# DAC_STM32_Board_v6_1_-_AD5391.net
KiCad netlist of a schematic drawn in EAGLE
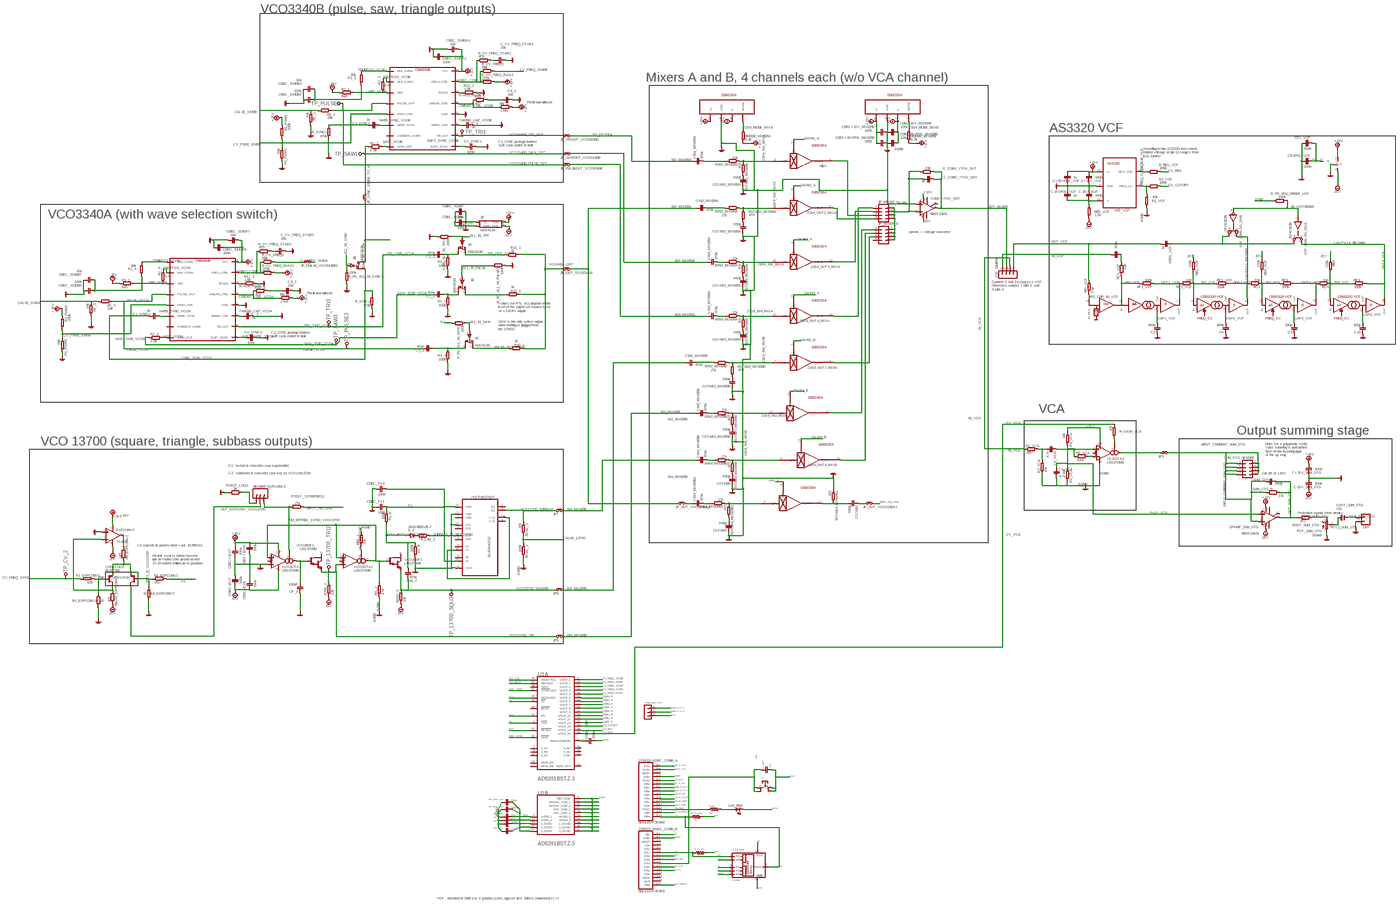
[diagram p0: schematic, sheet 1, overview]
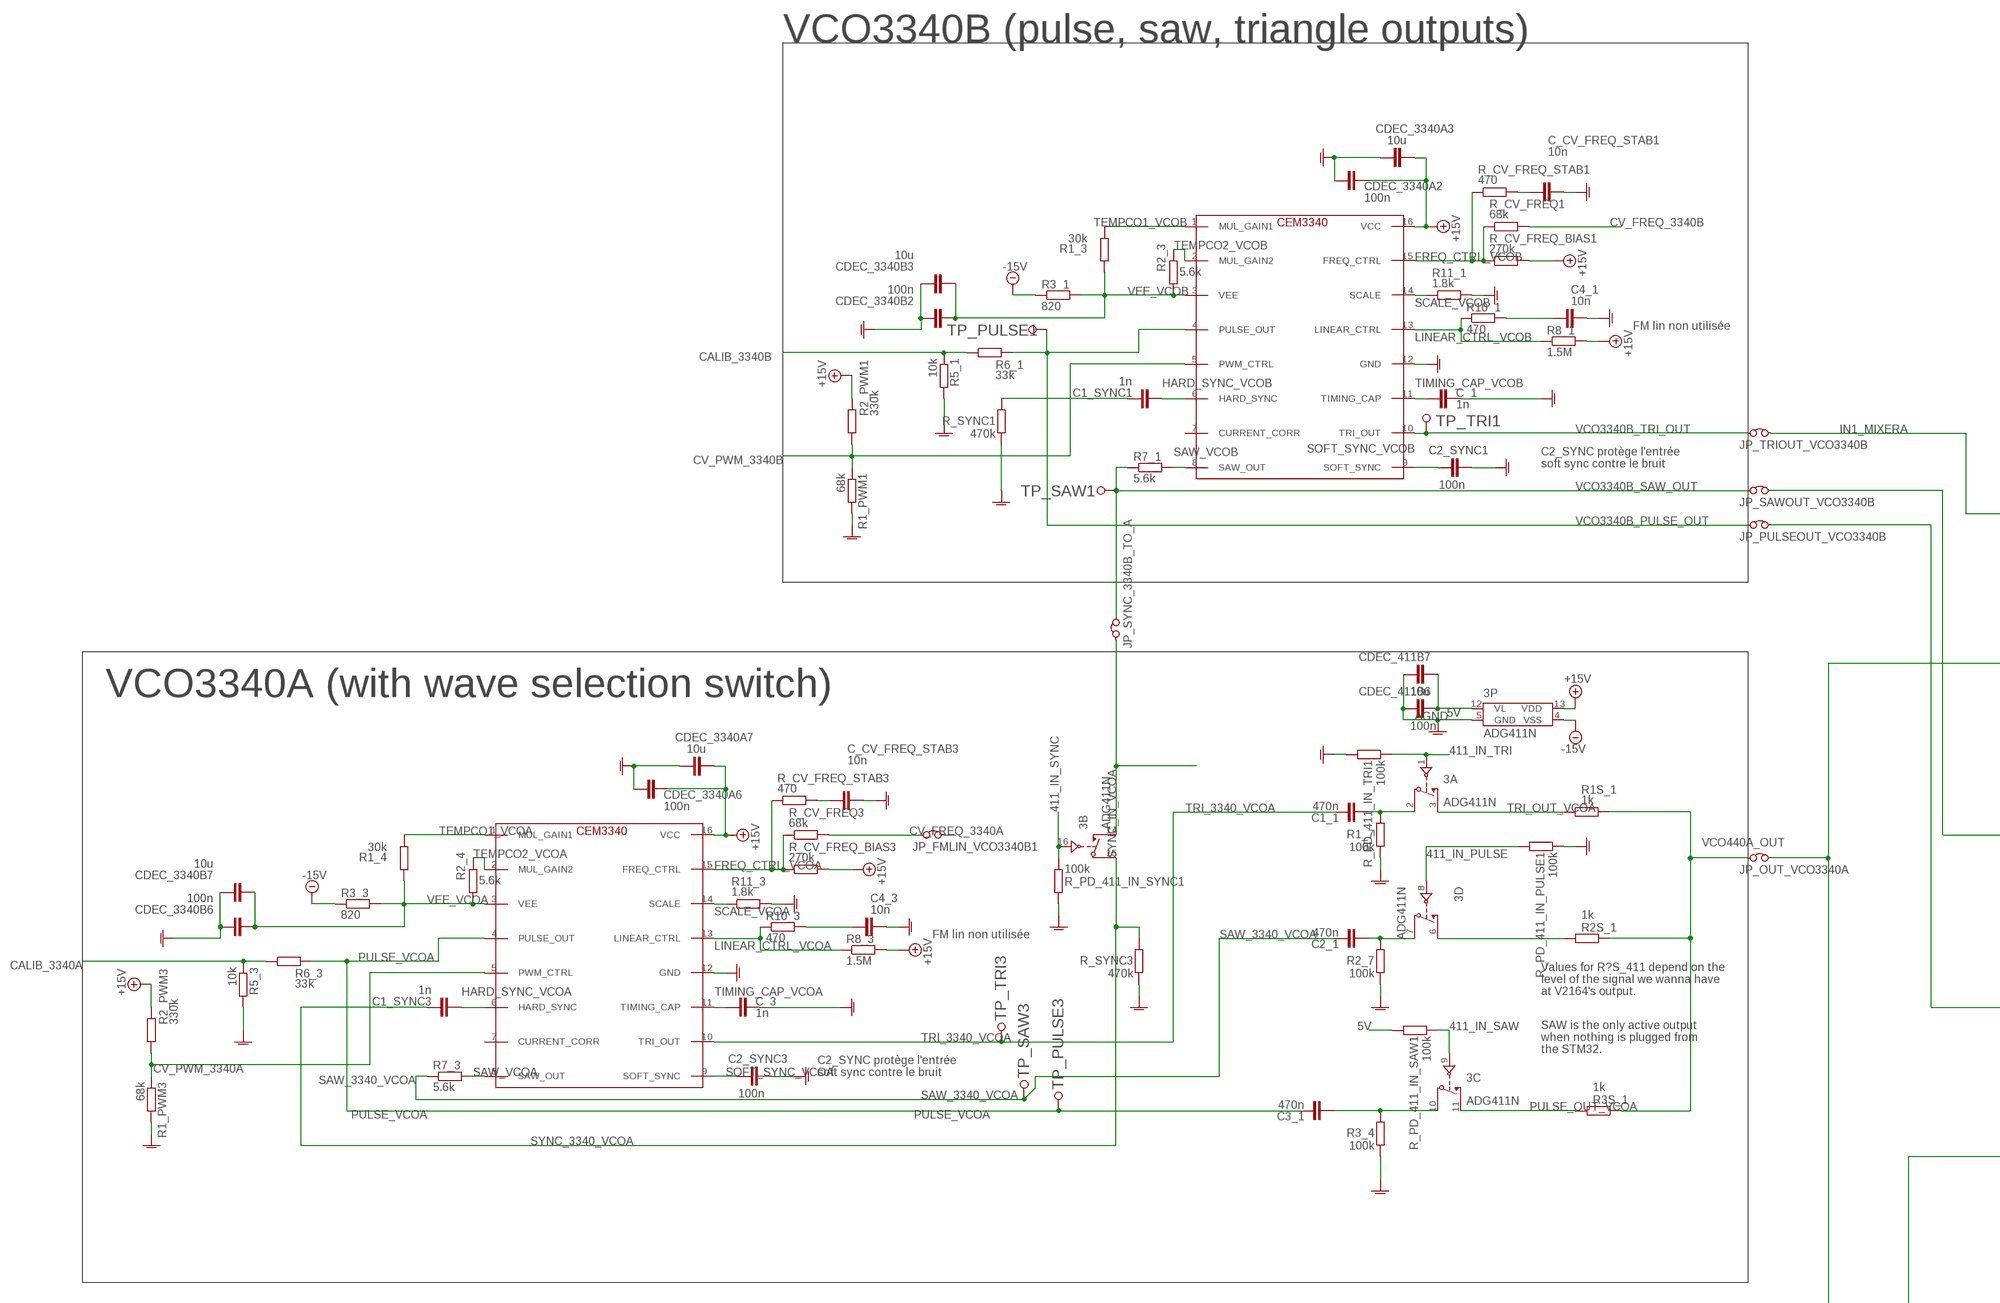
[diagram p1: schematic, sheet 1, part 1 of 4]
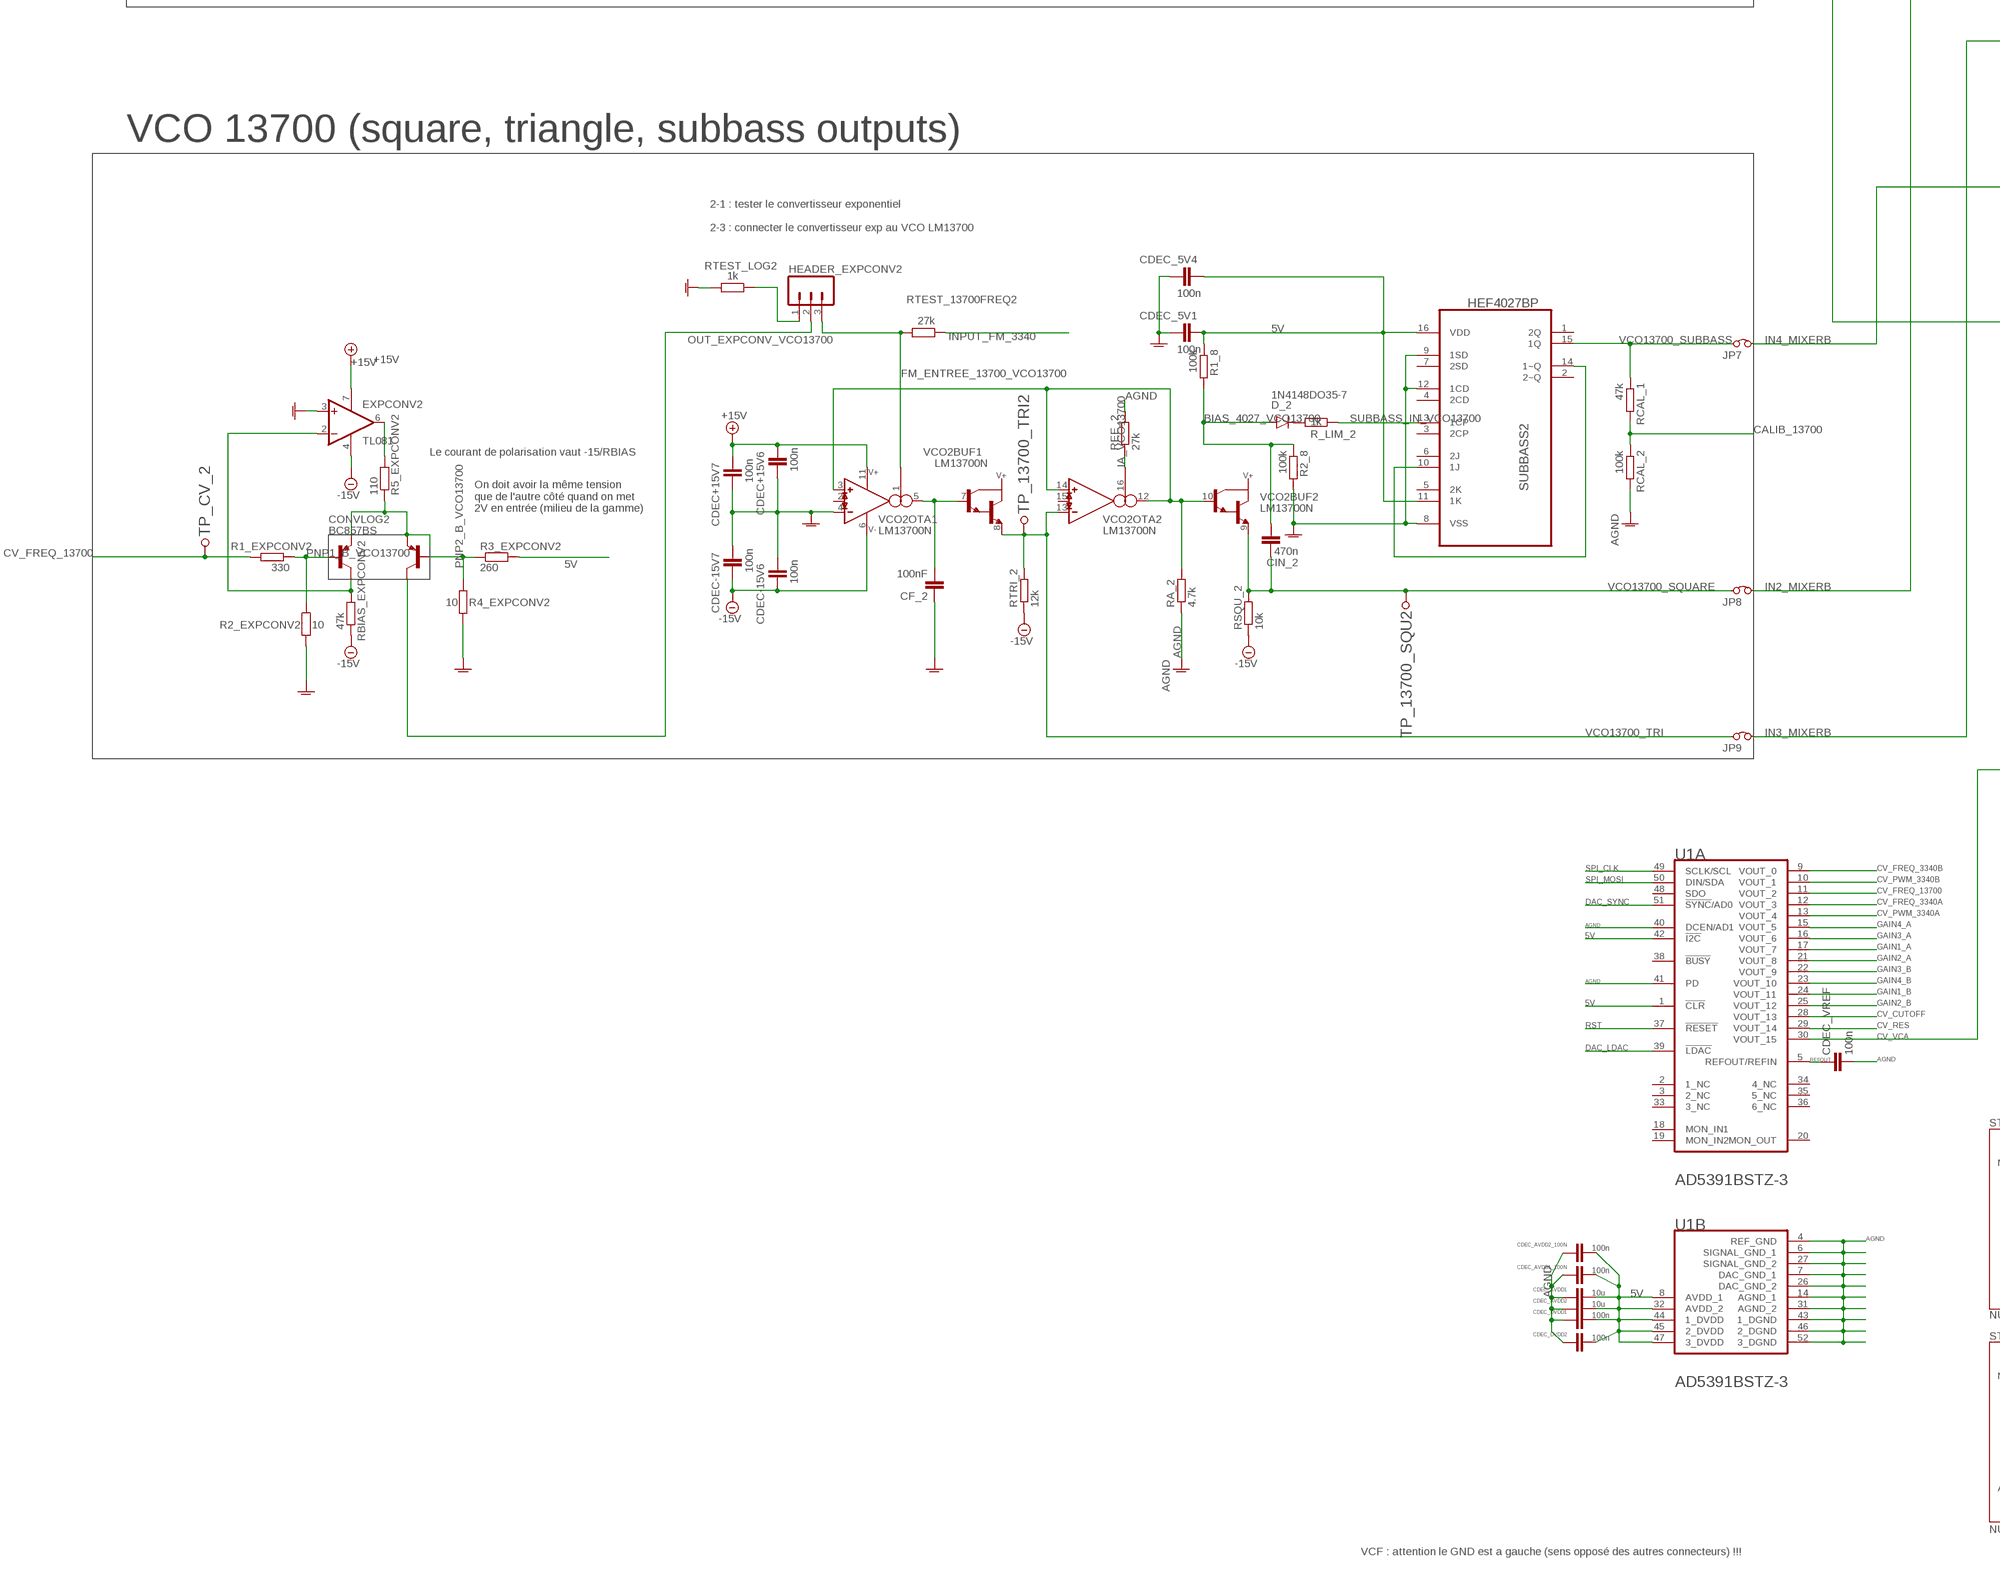
[diagram p2: schematic, sheet 1, part 2 of 4]
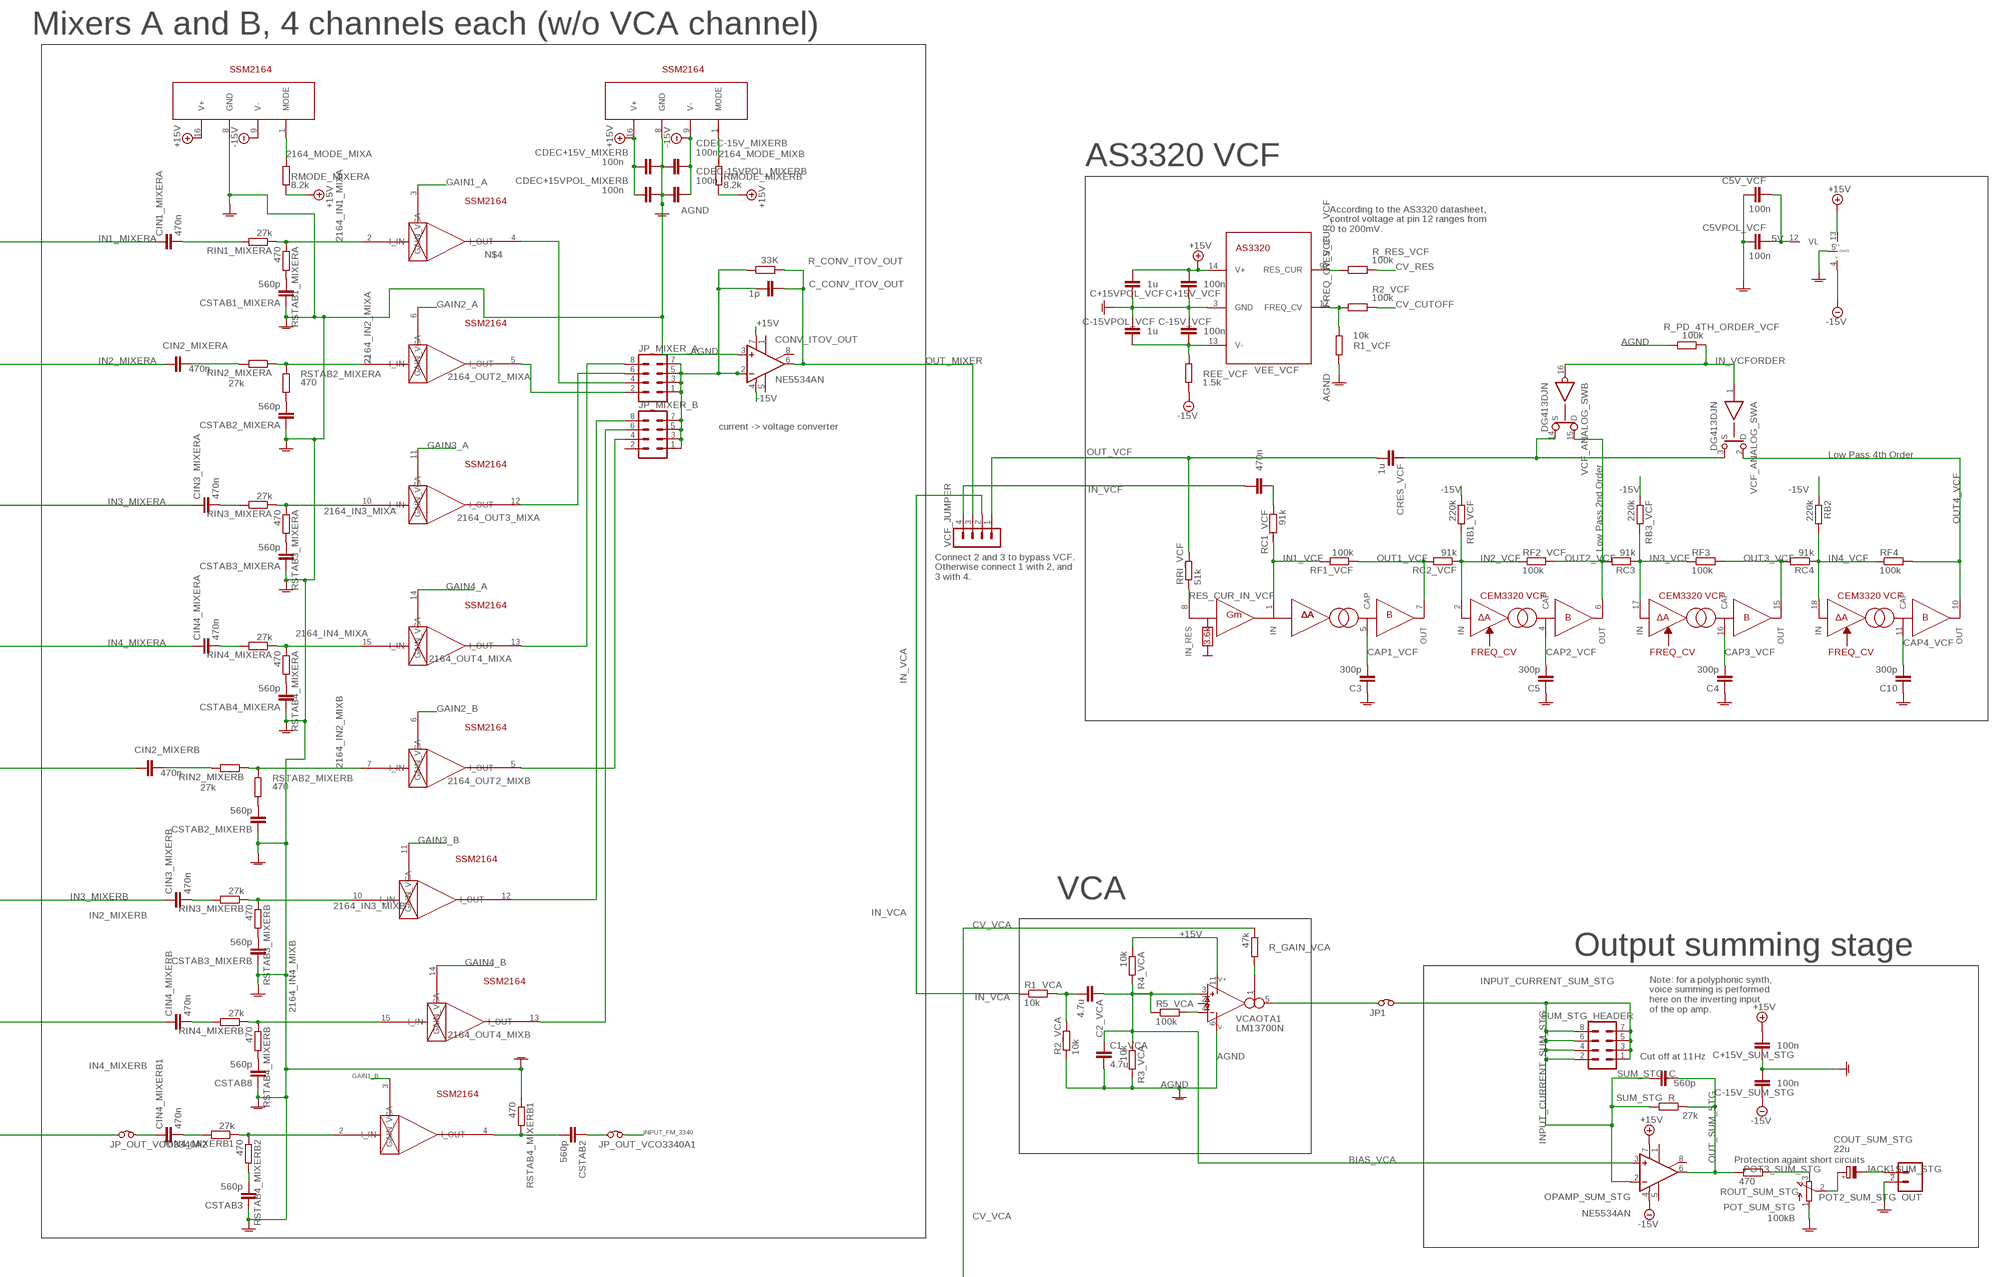
[diagram p3: schematic, sheet 1, part 3 of 4]
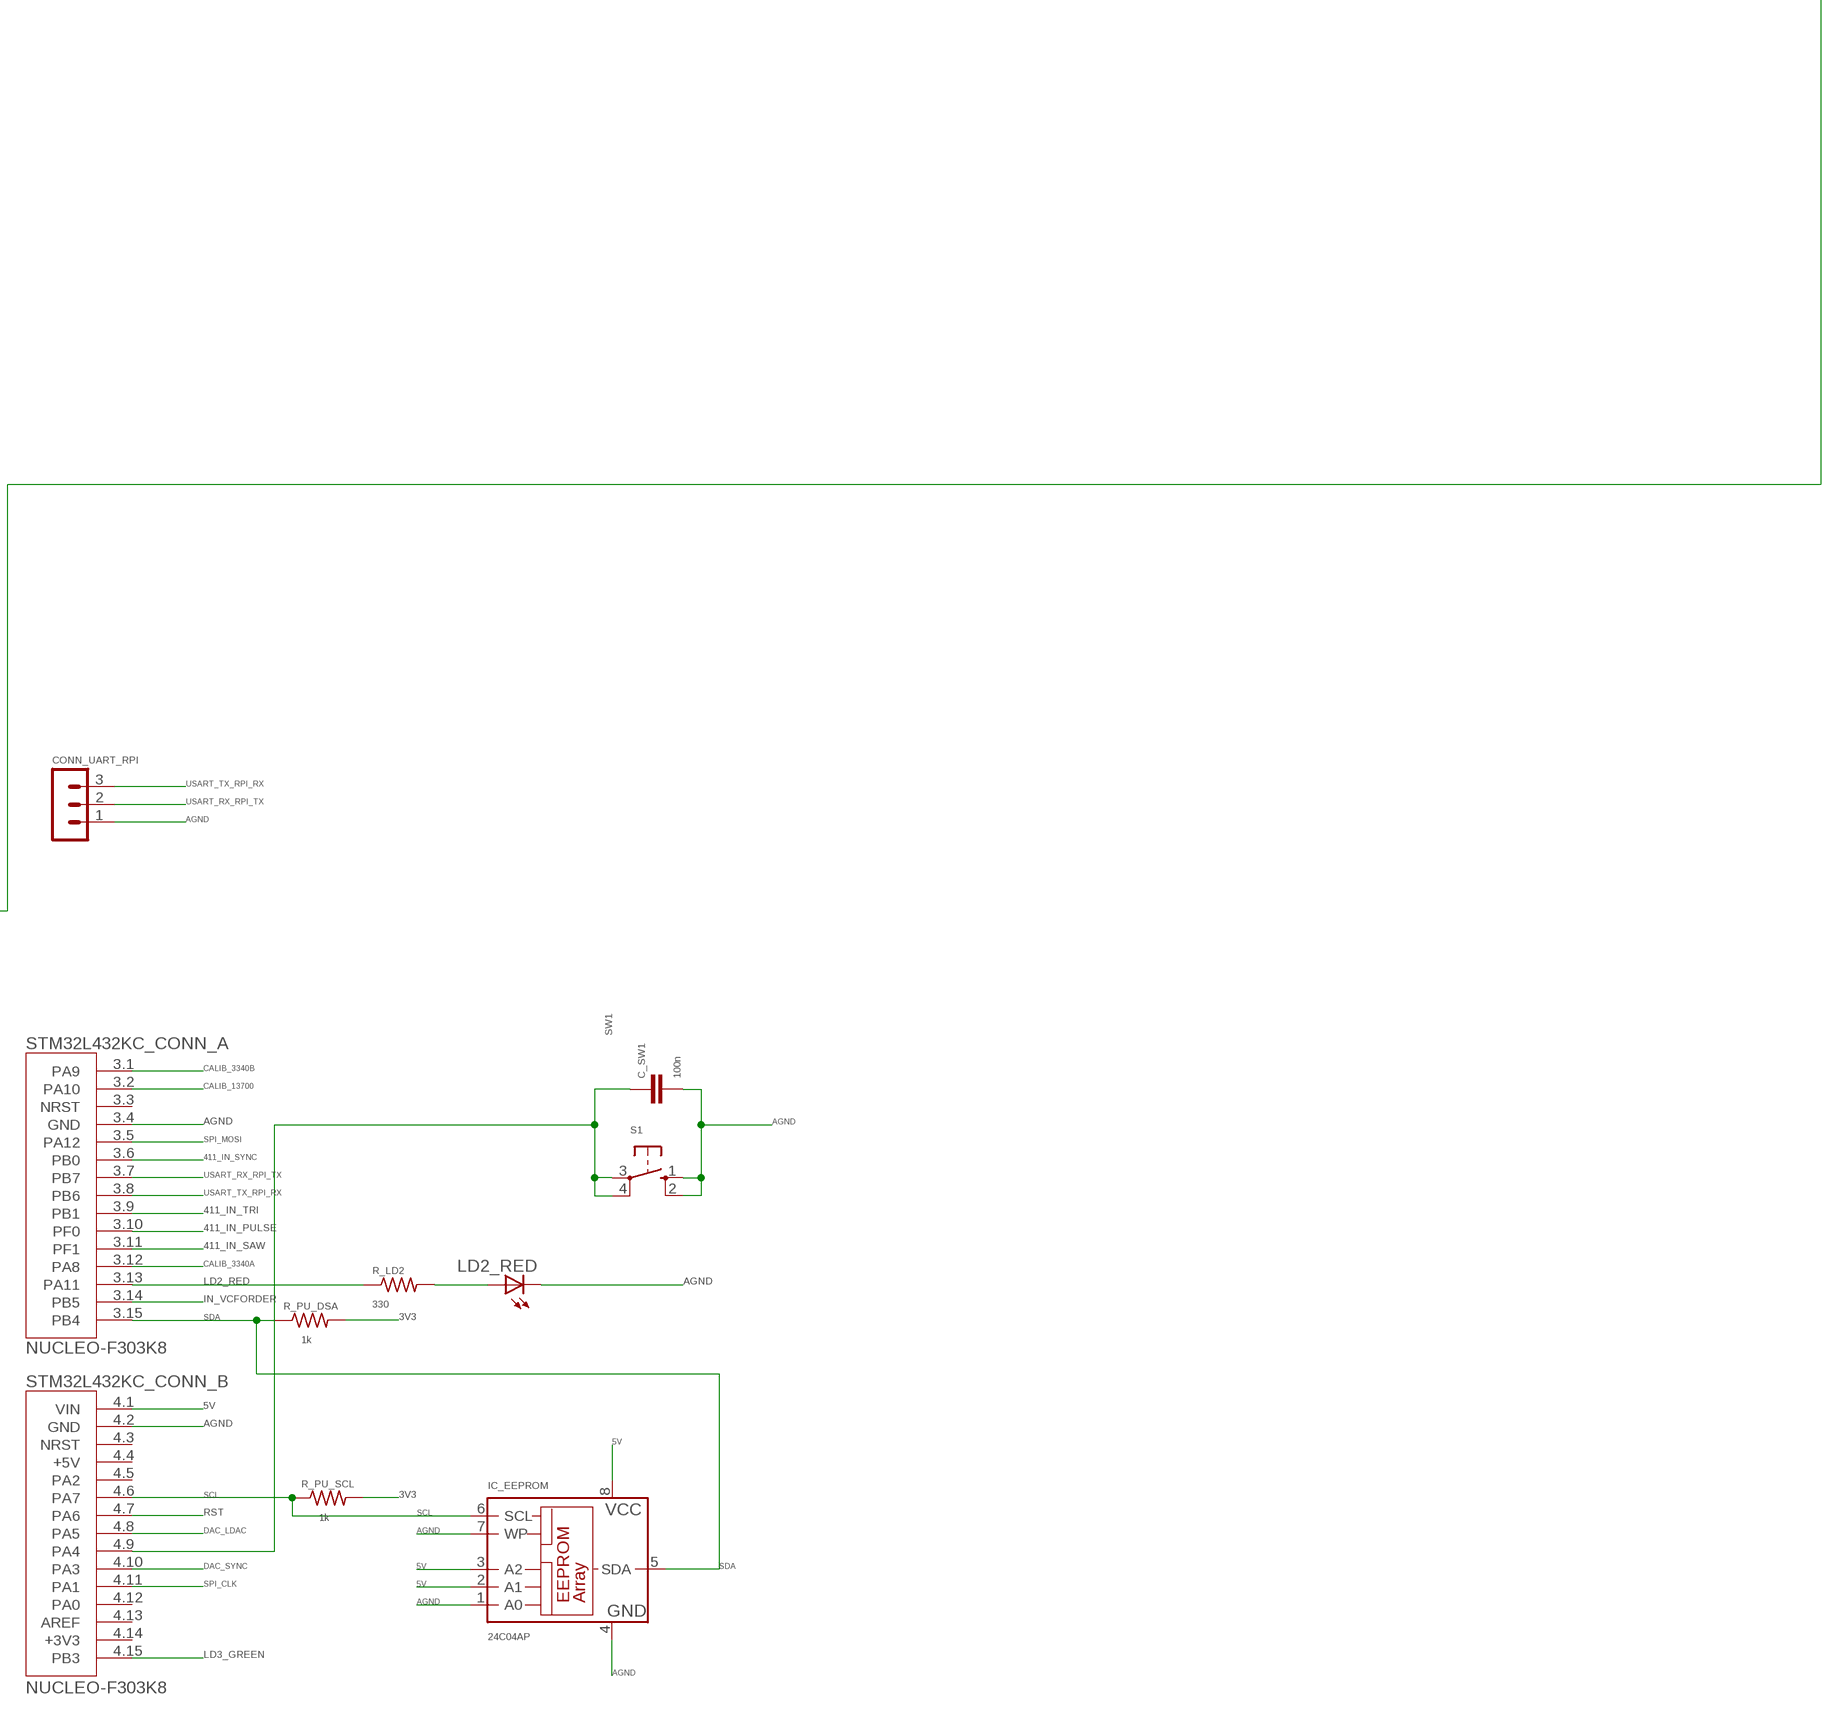
[diagram p4: schematic, sheet 1, part 4 of 4]

(export (version "E")
  (design (tool "Eeschema 10.0.6"))
  (components
    (comp (ref "3")
      (value "ADG411N")
      (footprint "eagle-import:DIL16")
      (fields (field (name "MF") "ALTERA CORPORATION") (field (name "MPN") "ADG411BN"))
      (libsource (lib "eagle-import") (part "ADG411N"))
    )
    (comp (ref "3340A")
      (value "CEM3340")
      (footprint "eagle-import:DIL16")
      (libsource (lib "eagle-import") (part "CEM3340"))
    )
    (comp (ref "3340B")
      (value "CEM3340")
      (footprint "eagle-import:DIL16")
      (libsource (lib "eagle-import") (part "CEM3340"))
    )
    (comp (ref "C+15VPOL_VCF")
      (value "1u")
      (footprint "eagle-import:C075-032X103")
      (libsource (lib "eagle-import") (part "rcl_334_C-EU075-032X103"))
    )
    (comp (ref "C+15V_SUM_STG")
      (value "100n")
      (footprint "eagle-import:C075-032X103")
      (libsource (lib "eagle-import") (part "rcl_334_C-EU075-032X103"))
    )
    (comp (ref "C+15V_VCF")
      (value "100n")
      (footprint "eagle-import:C075-032X103")
      (libsource (lib "eagle-import") (part "rcl_334_C-EU075-032X103"))
    )
    (comp (ref "C-15VPOL_VCF")
      (value "1u")
      (footprint "eagle-import:C075-032X103")
      (libsource (lib "eagle-import") (part "rcl_334_C-EU075-032X103"))
    )
    (comp (ref "C-15V_SUM_STG")
      (value "100n")
      (footprint "eagle-import:C075-032X103")
      (libsource (lib "eagle-import") (part "rcl_334_C-EU075-032X103"))
    )
    (comp (ref "C-15V_VCF")
      (value "100n")
      (footprint "eagle-import:C075-032X103")
      (libsource (lib "eagle-import") (part "rcl_334_C-EU075-032X103"))
    )
    (comp (ref "C1_1")
      (value "470n")
      (footprint "eagle-import:C075-032X103")
      (libsource (lib "eagle-import") (part "rcl_334_C-EU075-032X103"))
    )
    (comp (ref "C1_SYNC1")
      (value "1n")
      (footprint "eagle-import:C075-032X103")
      (libsource (lib "eagle-import") (part "rcl_334_C-EU075-032X103"))
    )
    (comp (ref "C1_SYNC3")
      (value "1n")
      (footprint "eagle-import:C075-032X103")
      (libsource (lib "eagle-import") (part "rcl_334_C-EU075-032X103"))
    )
    (comp (ref "C1_VCA")
      (value "4.7u")
      (footprint "eagle-import:C050-030X075")
      (libsource (lib "eagle-import") (part "rcl_334_C-EU050-030X075"))
    )
    (comp (ref "C2_1")
      (value "470n")
      (footprint "eagle-import:C075-032X103")
      (libsource (lib "eagle-import") (part "rcl_334_C-EU075-032X103"))
    )
    (comp (ref "C2_SYNC1")
      (value "100n")
      (footprint "eagle-import:C075-032X103")
      (libsource (lib "eagle-import") (part "rcl_334_C-EU075-032X103"))
    )
    (comp (ref "C2_SYNC3")
      (value "100n")
      (footprint "eagle-import:C050-025X075")
      (libsource (lib "eagle-import") (part "rcl_334_C-EU050-025X075"))
    )
    (comp (ref "C2_VCA")
      (value "4.7u")
      (footprint "eagle-import:C050-030X075")
      (libsource (lib "eagle-import") (part "rcl_334_C-EU050-030X075"))
    )
    (comp (ref "C3")
      (value "300p")
      (footprint "eagle-import:C075-032X103")
      (libsource (lib "eagle-import") (part "rcl_334_C-EU075-032X103"))
    )
    (comp (ref "C3_1")
      (value "470n")
      (footprint "eagle-import:C102-043X133")
      (libsource (lib "eagle-import") (part "rcl_334_C-EU102-043X133"))
    )
    (comp (ref "C4")
      (value "300p")
      (footprint "eagle-import:C075-032X103")
      (libsource (lib "eagle-import") (part "rcl_334_C-EU075-032X103"))
    )
    (comp (ref "C4_1")
      (value "10n")
      (footprint "eagle-import:C050-025X075")
      (libsource (lib "eagle-import") (part "rcl_334_C-EU050-025X075"))
    )
    (comp (ref "C4_3")
      (value "10n")
      (footprint "eagle-import:C050-025X075")
      (libsource (lib "eagle-import") (part "rcl_334_C-EU050-025X075"))
    )
    (comp (ref "C5")
      (value "300p")
      (footprint "eagle-import:C075-032X103")
      (libsource (lib "eagle-import") (part "rcl_334_C-EU075-032X103"))
    )
    (comp (ref "C5VPOL_VCF")
      (value "100n")
      (footprint "eagle-import:C075-032X103")
      (libsource (lib "eagle-import") (part "rcl_334_C-EU075-032X103"))
    )
    (comp (ref "C5V_VCF")
      (value "100n")
      (footprint "eagle-import:C075-032X103")
      (libsource (lib "eagle-import") (part "rcl_334_C-EU075-032X103"))
    )
    (comp (ref "C10")
      (value "300p")
      (footprint "eagle-import:C075-032X103")
      (libsource (lib "eagle-import") (part "rcl_334_C-EU075-032X103"))
    )
    (comp (ref "CDEC+15V6")
      (value "100n")
      (footprint "eagle-import:C075-032X103")
      (libsource (lib "eagle-import") (part "rcl_334_C-EU075-032X103"))
    )
    (comp (ref "CDEC+15V7")
      (value "100n")
      (footprint "eagle-import:C050-025X075")
      (libsource (lib "eagle-import") (part "rcl_334_C-EU050-025X075"))
    )
    (comp (ref "CDEC+15VPOL_MIXERB")
      (value "100n")
      (footprint "eagle-import:C075-032X103")
      (libsource (lib "eagle-import") (part "rcl_334_C-EU075-032X103"))
    )
    (comp (ref "CDEC+15V_MIXERB")
      (value "100n")
      (footprint "eagle-import:C050-030X075")
      (libsource (lib "eagle-import") (part "rcl_334_C-EU050-030X075"))
    )
    (comp (ref "CDEC-15V6")
      (value "100n")
      (footprint "eagle-import:C050-025X075")
      (libsource (lib "eagle-import") (part "rcl_334_C-EU050-025X075"))
    )
    (comp (ref "CDEC-15V7")
      (value "100n")
      (footprint "eagle-import:C075-032X103")
      (libsource (lib "eagle-import") (part "rcl_334_C-EU075-032X103"))
    )
    (comp (ref "CDEC-15VPOL_MIXERB")
      (value "100n")
      (footprint "eagle-import:C050-030X075")
      (libsource (lib "eagle-import") (part "rcl_334_C-EU050-030X075"))
    )
    (comp (ref "CDEC-15V_MIXERB")
      (value "100n")
      (footprint "eagle-import:C050-030X075")
      (libsource (lib "eagle-import") (part "rcl_334_C-EU050-030X075"))
    )
    (comp (ref "CDEC_5V1")
      (value "100n")
      (footprint "eagle-import:C050-025X075")
      (libsource (lib "eagle-import") (part "rcl_334_C-EU050-025X075"))
    )
    (comp (ref "CDEC_5V4")
      (value "100n")
      (footprint "eagle-import:C050-025X075")
      (libsource (lib "eagle-import") (part "rcl_334_C-EU050-025X075"))
    )
    (comp (ref "CDEC_411B6")
      (value "100n")
      (footprint "eagle-import:C050-025X075")
      (libsource (lib "eagle-import") (part "rcl_334_C-EU050-025X075"))
    )
    (comp (ref "CDEC_411B7")
      (value "10u")
      (footprint "eagle-import:C050-025X075")
      (libsource (lib "eagle-import") (part "rcl_334_C-EU050-025X075"))
    )
    (comp (ref "CDEC_3340A2")
      (value "100n")
      (footprint "eagle-import:C050-025X075")
      (libsource (lib "eagle-import") (part "rcl_334_C-EU050-025X075"))
    )
    (comp (ref "CDEC_3340A3")
      (value "10u")
      (footprint "eagle-import:C075-032X103")
      (libsource (lib "eagle-import") (part "rcl_334_C-EU075-032X103"))
    )
    (comp (ref "CDEC_3340A6")
      (value "100n")
      (footprint "eagle-import:C050-025X075")
      (libsource (lib "eagle-import") (part "rcl_334_C-EU050-025X075"))
    )
    (comp (ref "CDEC_3340A7")
      (value "10u")
      (footprint "eagle-import:C050-025X075")
      (libsource (lib "eagle-import") (part "rcl_334_C-EU050-025X075"))
    )
    (comp (ref "CDEC_3340B2")
      (value "100n")
      (footprint "eagle-import:C050-025X075")
      (libsource (lib "eagle-import") (part "rcl_334_C-EU050-025X075"))
    )
    (comp (ref "CDEC_3340B3")
      (value "10u")
      (footprint "eagle-import:C050-025X075")
      (libsource (lib "eagle-import") (part "rcl_334_C-EU050-025X075"))
    )
    (comp (ref "CDEC_3340B6")
      (value "100n")
      (footprint "eagle-import:C050-025X075")
      (libsource (lib "eagle-import") (part "rcl_334_C-EU050-025X075"))
    )
    (comp (ref "CDEC_3340B7")
      (value "10u")
      (footprint "eagle-import:C050-025X075")
      (libsource (lib "eagle-import") (part "rcl_334_C-EU050-025X075"))
    )
    (comp (ref "CDEC_AVDD1")
      (value "10u")
      (footprint "eagle-import:C050-030X075")
      (libsource (lib "eagle-import") (part "C-EU050-030X075"))
    )
    (comp (ref "CDEC_AVDD1_100N")
      (value "100n")
      (footprint "eagle-import:C050-030X075")
      (libsource (lib "eagle-import") (part "C-EU050-030X075"))
    )
    (comp (ref "CDEC_AVDD2")
      (value "10u")
      (footprint "eagle-import:C050-030X075")
      (libsource (lib "eagle-import") (part "C-EU050-030X075"))
    )
    (comp (ref "CDEC_AVDD2_100N")
      (value "100n")
      (footprint "eagle-import:C050-030X075")
      (libsource (lib "eagle-import") (part "C-EU050-030X075"))
    )
    (comp (ref "CDEC_DVDD1")
      (value "100n")
      (footprint "eagle-import:C075-032X103")
      (libsource (lib "eagle-import") (part "C-EU075-032X103"))
    )
    (comp (ref "CDEC_DVDD2")
      (value "100n")
      (footprint "eagle-import:C050-030X075")
      (libsource (lib "eagle-import") (part "C-EU050-030X075"))
    )
    (comp (ref "CDEC_VREF")
      (value "100n")
      (footprint "eagle-import:C050-030X075")
      (libsource (lib "eagle-import") (part "C-EU050-030X075"))
    )
    (comp (ref "CF_2")
      (value "100nF")
      (footprint "eagle-import:C050-025X075")
      (libsource (lib "eagle-import") (part "rcl_334_C-EU050-025X075"))
    )
    (comp (ref "CIN1_MIXERA")
      (value "470n")
      (footprint "eagle-import:C050-030X075")
      (fields (field (name "C3") "0.47 micro"))
      (libsource (lib "eagle-import") (part "rcl_334_C-EU050-030X075"))
    )
    (comp (ref "CIN2_MIXERA")
      (value "470n")
      (footprint "eagle-import:C050-030X075")
      (fields (field (name "C3") "0.47 micro"))
      (libsource (lib "eagle-import") (part "rcl_334_C-EU050-030X075"))
    )
    (comp (ref "CIN2_MIXERB")
      (value "470n")
      (footprint "eagle-import:C050-030X075")
      (fields (field (name "C3") "0.47 micro"))
      (libsource (lib "eagle-import") (part "rcl_334_C-EU050-030X075"))
    )
    (comp (ref "CIN3_MIXERA")
      (value "470n")
      (footprint "eagle-import:C050-030X075")
      (fields (field (name "C3") "0.47 micro"))
      (libsource (lib "eagle-import") (part "rcl_334_C-EU050-030X075"))
    )
    (comp (ref "CIN3_MIXERB")
      (value "470n")
      (footprint "eagle-import:C050-030X075")
      (fields (field (name "C3") "0.47 micro"))
      (libsource (lib "eagle-import") (part "rcl_334_C-EU050-030X075"))
    )
    (comp (ref "CIN4_MIXERA")
      (value "470n")
      (footprint "eagle-import:C050-030X075")
      (fields (field (name "C3") "0.47 micro"))
      (libsource (lib "eagle-import") (part "rcl_334_C-EU050-030X075"))
    )
    (comp (ref "CIN4_MIXERB")
      (value "470n")
      (footprint "eagle-import:C050-030X075")
      (fields (field (name "C3") "0.47 micro"))
      (libsource (lib "eagle-import") (part "rcl_334_C-EU050-030X075"))
    )
    (comp (ref "CIN4_MIXERB1")
      (value "470n")
      (footprint "eagle-import:C050-030X075")
      (fields (field (name "C3") "0.47 micro"))
      (libsource (lib "eagle-import") (part "rcl_334_C-EU050-030X075"))
    )
    (comp (ref "CIN_2")
      (value "470n")
      (footprint "eagle-import:C050-025X075")
      (libsource (lib "eagle-import") (part "rcl_334_C-EU050-025X075"))
    )
    (comp (ref "CONN_UART_RPI")
      (value "MA03-1")
      (footprint "eagle-import:MA03-1")
      (libsource (lib "eagle-import") (part "MA03-1"))
    )
    (comp (ref "CONVLOG2")
      (value "BC857BS")
      (footprint "eagle-import:DIL06")
      (libsource (lib "eagle-import") (part "BC857BS"))
    )
    (comp (ref "CONV_ITOV_OUT")
      (value "NE5534AN")
      (footprint "eagle-import:DIL08")
      (libsource (lib "eagle-import") (part "linear_262_NE5534NA"))
    )
    (comp (ref "COUT_SUM_STG")
      (value "22u")
      (footprint "eagle-import:B45181A")
      (libsource (lib "eagle-import") (part "CPOL-EUB45181A"))
    )
    (comp (ref "CRES_VCF")
      (value "1u")
      (footprint "eagle-import:C075-032X103")
      (libsource (lib "eagle-import") (part "rcl_334_C-EU075-032X103"))
    )
    (comp (ref "CSTAB1_MIXERA")
      (value "560p")
      (footprint "eagle-import:C050-030X075")
      (libsource (lib "eagle-import") (part "rcl_334_C-EU050-030X075"))
    )
    (comp (ref "CSTAB2")
      (value "560p")
      (footprint "eagle-import:C050-030X075")
      (libsource (lib "eagle-import") (part "rcl_334_C-EU050-030X075"))
    )
    (comp (ref "CSTAB2_MIXERA")
      (value "560p")
      (footprint "eagle-import:C050-030X075")
      (libsource (lib "eagle-import") (part "rcl_334_C-EU050-030X075"))
    )
    (comp (ref "CSTAB2_MIXERB")
      (value "560p")
      (footprint "eagle-import:C050-030X075")
      (libsource (lib "eagle-import") (part "rcl_334_C-EU050-030X075"))
    )
    (comp (ref "CSTAB3")
      (value "560p")
      (footprint "eagle-import:C050-030X075")
      (libsource (lib "eagle-import") (part "rcl_334_C-EU050-030X075"))
    )
    (comp (ref "CSTAB3_MIXERA")
      (value "560p")
      (footprint "eagle-import:C050-030X075")
      (libsource (lib "eagle-import") (part "rcl_334_C-EU050-030X075"))
    )
    (comp (ref "CSTAB3_MIXERB")
      (value "560p")
      (footprint "eagle-import:C050-030X075")
      (libsource (lib "eagle-import") (part "rcl_334_C-EU050-030X075"))
    )
    (comp (ref "CSTAB4_MIXERA")
      (value "560p")
      (footprint "eagle-import:C050-030X075")
      (libsource (lib "eagle-import") (part "rcl_334_C-EU050-030X075"))
    )
    (comp (ref "CSTAB8")
      (value "560p")
      (footprint "eagle-import:C050-030X075")
      (libsource (lib "eagle-import") (part "rcl_334_C-EU050-030X075"))
    )
    (comp (ref "C_1")
      (value "1n")
      (footprint "eagle-import:C050-025X075")
      (libsource (lib "eagle-import") (part "rcl_334_C-EU050-025X075"))
    )
    (comp (ref "C_3")
      (value "1n")
      (footprint "eagle-import:C050-025X075")
      (libsource (lib "eagle-import") (part "rcl_334_C-EU050-025X075"))
    )
    (comp (ref "C_CONV_ITOV_OUT")
      (value "1p")
      (footprint "eagle-import:C050-030X075")
      (fields (field (name "C3") "0.47 micro"))
      (libsource (lib "eagle-import") (part "rcl_334_C-EU050-030X075"))
    )
    (comp (ref "C_CV_FREQ_STAB1")
      (value "10n")
      (footprint "eagle-import:C075-032X103")
      (libsource (lib "eagle-import") (part "rcl_334_C-EU075-032X103"))
    )
    (comp (ref "C_CV_FREQ_STAB3")
      (value "10n")
      (footprint "eagle-import:C075-032X103")
      (libsource (lib "eagle-import") (part "rcl_334_C-EU075-032X103"))
    )
    (comp (ref "C_IN2")
      (value "470n")
      (footprint "eagle-import:C050-025X075")
      (libsource (lib "eagle-import") (part "rcl_334_C-EU050-025X075"))
    )
    (comp (ref "C_SW1")
      (value "100n")
      (footprint "eagle-import:C050-030X075")
      (libsource (lib "eagle-import") (part "C-EU050-030X075"))
    )
    (comp (ref "D_2")
      (value "1N4148DO35-7")
      (footprint "eagle-import:DO35-7")
      (libsource (lib "eagle-import") (part "1N4148DO35-7"))
    )
    (comp (ref "EXPCONV2")
      (value "TL081")
      (footprint "eagle-import:DIL08")
      (libsource (lib "eagle-import") (part "1AMP_P7+4N"))
    )
    (comp (ref "HEADER_EXPCONV2")
      (value "M03")
      (footprint "eagle-import:03P")
      (libsource (lib "eagle-import") (part "M03"))
    )
    (comp (ref "IC_EEPROM")
      (value "24C04AP")
      (footprint "eagle-import:DIL8")
      (fields (field (name "MPN") "AT24C04B-PU"))
      (libsource (lib "eagle-import") (part "24CP04A"))
    )
    (comp (ref "JP1")
      (value "JUMPER")
      (footprint "eagle-import:HDR2X1")
      (libsource (lib "eagle-import") (part "JUMPER"))
    )
    (comp (ref "JP7")
      (value "JUMPER")
      (footprint "eagle-import:HDR2X1")
      (libsource (lib "eagle-import") (part "JUMPER"))
    )
    (comp (ref "JP8")
      (value "JUMPER")
      (footprint "eagle-import:HDR2X1")
      (libsource (lib "eagle-import") (part "JUMPER"))
    )
    (comp (ref "JP9")
      (value "JUMPER")
      (footprint "eagle-import:HDR2X1")
      (libsource (lib "eagle-import") (part "JUMPER"))
    )
    (comp (ref "JP_FMLIN_VCO3340B1")
      (value "JUMPER")
      (footprint "eagle-import:HDR2X1")
      (libsource (lib "eagle-import") (part "JUMPER"))
    )
    (comp (ref "JP_MIXER_A")
      (value "MA04-2")
      (footprint "eagle-import:MA04-2")
      (libsource (lib "eagle-import") (part "MA04-2"))
    )
    (comp (ref "JP_MIXER_B")
      (value "MA04-2")
      (footprint "eagle-import:MA04-2")
      (libsource (lib "eagle-import") (part "MA04-2"))
    )
    (comp (ref "JP_OUT_VCO3340A")
      (value "JUMPER")
      (footprint "eagle-import:HDR2X1")
      (libsource (lib "eagle-import") (part "JUMPER"))
    )
    (comp (ref "JP_OUT_VCO3340A1")
      (value "JUMPER")
      (footprint "eagle-import:HDR2X1")
      (libsource (lib "eagle-import") (part "JUMPER"))
    )
    (comp (ref "JP_OUT_VCO3340A2")
      (value "JUMPER")
      (footprint "eagle-import:HDR2X1")
      (libsource (lib "eagle-import") (part "JUMPER"))
    )
    (comp (ref "JP_PULSEOUT_VCO3340B")
      (value "JUMPER")
      (footprint "eagle-import:HDR2X1")
      (libsource (lib "eagle-import") (part "JUMPER"))
    )
    (comp (ref "JP_SAWOUT_VCO3340B")
      (value "JUMPER")
      (footprint "eagle-import:HDR2X1")
      (libsource (lib "eagle-import") (part "JUMPER"))
    )
    (comp (ref "JP_SYNC_3340B_TO_A")
      (value "JUMPER")
      (footprint "eagle-import:HDR2X1")
      (libsource (lib "eagle-import") (part "JUMPER"))
    )
    (comp (ref "JP_TRIOUT_VCO3340B")
      (value "JUMPER")
      (footprint "eagle-import:HDR2X1")
      (libsource (lib "eagle-import") (part "JUMPER"))
    )
    (comp (ref "LD2_RED")
      (value "LED3MM")
      (footprint "eagle-import:LED3MM")
      (libsource (lib "eagle-import") (part "LED3MM"))
    )
    (comp (ref "MIXER_A")
      (value "SSM2164_MULTI")
      (footprint "eagle-import:DIL16")
      (libsource (lib "eagle-import") (part "SSM2164_MULTI"))
    )
    (comp (ref "MIXER_B")
      (value "SSM2164_MULTI")
      (footprint "eagle-import:DIL16")
      (libsource (lib "eagle-import") (part "SSM2164_MULTI"))
    )
    (comp (ref "OPAMP_SUM_STG")
      (value "NE5534AN")
      (footprint "eagle-import:DIL08")
      (libsource (lib "eagle-import") (part "NE5534NA"))
    )
    (comp (ref "OUT")
      (value "MA02")
      (footprint "eagle-import:02PA")
      (libsource (lib "eagle-import") (part "MA02"))
    )
    (comp (ref "POT_SUM_STG")
      (value "100kB")
      (footprint "eagle-import:3RP_1610N")
      (libsource (lib "eagle-import") (part "3RP/1610N"))
    )
    (comp (ref "R1S_1")
      (value "1k")
      (footprint "eagle-import:0204_7")
      (libsource (lib "eagle-import") (part "R-EU_0204/7"))
    )
    (comp (ref "R1_3")
      (value "30k")
      (footprint "eagle-import:0204_7")
      (libsource (lib "eagle-import") (part "R-EU_0204/7"))
    )
    (comp (ref "R1_4")
      (value "30k")
      (footprint "eagle-import:0204_7")
      (libsource (lib "eagle-import") (part "R-EU_0204/7"))
    )
    (comp (ref "R1_7")
      (value "100k")
      (footprint "eagle-import:0204_7")
      (libsource (lib "eagle-import") (part "R-EU_0204/7"))
    )
    (comp (ref "R1_8")
      (value "100k")
      (footprint "eagle-import:0204_7")
      (libsource (lib "eagle-import") (part "R-EU_0204/7"))
    )
    (comp (ref "R1_EXPCONV2")
      (value "330")
      (footprint "eagle-import:0204_7")
      (libsource (lib "eagle-import") (part "R-EU_0204/7"))
    )
    (comp (ref "R1_PWM1")
      (value "68k")
      (footprint "eagle-import:0204_7")
      (libsource (lib "eagle-import") (part "R-EU_0204/7"))
    )
    (comp (ref "R1_PWM3")
      (value "68k")
      (footprint "eagle-import:0207_10")
      (libsource (lib "eagle-import") (part "R-EU_0207/10"))
    )
    (comp (ref "R1_VCA")
      (value "10k")
      (footprint "eagle-import:0204_7")
      (libsource (lib "eagle-import") (part "R-EU_0204/7"))
    )
    (comp (ref "R1_VCF")
      (value "10k")
      (footprint "eagle-import:0204_7")
      (libsource (lib "eagle-import") (part "R-EU_0204/7"))
    )
    (comp (ref "R2S_1")
      (value "1k")
      (footprint "eagle-import:0204_7")
      (libsource (lib "eagle-import") (part "R-EU_0204/7"))
    )
    (comp (ref "R2_3")
      (value "5.6k")
      (footprint "eagle-import:0204_7")
      (libsource (lib "eagle-import") (part "R-EU_0204/7"))
    )
    (comp (ref "R2_4")
      (value "5.6k")
      (footprint "eagle-import:0204_7")
      (libsource (lib "eagle-import") (part "R-EU_0204/7"))
    )
    (comp (ref "R2_7")
      (value "100k")
      (footprint "eagle-import:0207_10")
      (libsource (lib "eagle-import") (part "R-EU_0207/10"))
    )
    (comp (ref "R2_8")
      (value "100k")
      (footprint "eagle-import:0204_7")
      (libsource (lib "eagle-import") (part "R-EU_0204/7"))
    )
    (comp (ref "R2_EXPCONV2")
      (value "10")
      (footprint "eagle-import:0204_7")
      (libsource (lib "eagle-import") (part "R-EU_0204/7"))
    )
    (comp (ref "R2_PWM1")
      (value "330k")
      (footprint "eagle-import:0204_7")
      (libsource (lib "eagle-import") (part "R-EU_0204/7"))
    )
    (comp (ref "R2_PWM3")
      (value "330k")
      (footprint "eagle-import:0204_7")
      (libsource (lib "eagle-import") (part "R-EU_0204/7"))
    )
    (comp (ref "R2_VCA")
      (value "10k")
      (footprint "eagle-import:0204_7")
      (libsource (lib "eagle-import") (part "R-EU_0204/7"))
    )
    (comp (ref "R2_VCF")
      (value "100k")
      (footprint "eagle-import:0204_7")
      (libsource (lib "eagle-import") (part "R-EU_0204/7"))
    )
    (comp (ref "R3S_1")
      (value "1k")
      (footprint "eagle-import:0207_10")
      (libsource (lib "eagle-import") (part "R-EU_0207/10"))
    )
    (comp (ref "R3_1")
      (value "820")
      (footprint "eagle-import:0204_7")
      (libsource (lib "eagle-import") (part "R-EU_0204/7"))
    )
    (comp (ref "R3_3")
      (value "820")
      (footprint "eagle-import:0204_7")
      (libsource (lib "eagle-import") (part "R-EU_0204/7"))
    )
    (comp (ref "R3_4")
      (value "100k")
      (footprint "eagle-import:0207_10")
      (libsource (lib "eagle-import") (part "R-EU_0207/10"))
    )
    (comp (ref "R3_EXPCONV2")
      (value "260")
      (footprint "eagle-import:0204_7")
      (libsource (lib "eagle-import") (part "R-EU_0204/7"))
    )
    (comp (ref "R3_VCA")
      (value "10k")
      (footprint "eagle-import:0204_7")
      (libsource (lib "eagle-import") (part "R-EU_0204/7"))
    )
    (comp (ref "R4_EXPCONV2")
      (value "10")
      (footprint "eagle-import:0204_7")
      (libsource (lib "eagle-import") (part "R-EU_0204/7"))
    )
    (comp (ref "R4_VCA")
      (value "10k")
      (footprint "eagle-import:0204_7")
      (libsource (lib "eagle-import") (part "R-EU_0204/7"))
    )
    (comp (ref "R5_1")
      (value "10k")
      (footprint "eagle-import:0204_7")
      (libsource (lib "eagle-import") (part "R-EU_0204/7"))
    )
    (comp (ref "R5_3")
      (value "10k")
      (footprint "eagle-import:0204_7")
      (libsource (lib "eagle-import") (part "R-EU_0204/7"))
    )
    (comp (ref "R5_EXPCONV2")
      (value "110")
      (footprint "eagle-import:0204_7")
      (libsource (lib "eagle-import") (part "R-EU_0204/7"))
    )
    (comp (ref "R5_VCA")
      (value "100k")
      (footprint "eagle-import:0204_7")
      (libsource (lib "eagle-import") (part "R-EU_0204/7"))
    )
    (comp (ref "R6_1")
      (value "33k")
      (footprint "eagle-import:0204_7")
      (libsource (lib "eagle-import") (part "R-EU_0204/7"))
    )
    (comp (ref "R6_3")
      (value "33k")
      (footprint "eagle-import:0204_7")
      (libsource (lib "eagle-import") (part "R-EU_0204/7"))
    )
    (comp (ref "R7_1")
      (value "5.6k")
      (footprint "eagle-import:0207_10")
      (libsource (lib "eagle-import") (part "R-EU_0207/10"))
    )
    (comp (ref "R7_3")
      (value "5.6k")
      (footprint "eagle-import:0207_10")
      (libsource (lib "eagle-import") (part "R-EU_0207/10"))
    )
    (comp (ref "R8_1")
      (value "1.5M")
      (footprint "eagle-import:0204_7")
      (libsource (lib "eagle-import") (part "R-EU_0204/7"))
    )
    (comp (ref "R8_3")
      (value "1.5M")
      (footprint "eagle-import:0204_7")
      (libsource (lib "eagle-import") (part "R-EU_0204/7"))
    )
    (comp (ref "R10_1")
      (value "470")
      (footprint "eagle-import:0204_7")
      (libsource (lib "eagle-import") (part "R-EU_0204/7"))
    )
    (comp (ref "R10_3")
      (value "470")
      (footprint "eagle-import:0204_7")
      (libsource (lib "eagle-import") (part "R-EU_0204/7"))
    )
    (comp (ref "R11_1")
      (value "1.8k")
      (footprint "eagle-import:0204_7")
      (libsource (lib "eagle-import") (part "R-EU_0204/7"))
    )
    (comp (ref "R11_3")
      (value "1.8k")
      (footprint "eagle-import:0204_7")
      (libsource (lib "eagle-import") (part "R-EU_0204/7"))
    )
    (comp (ref "RA_2")
      (value "4.7k")
      (footprint "eagle-import:0204_7")
      (libsource (lib "eagle-import") (part "R-EU_0204/7"))
    )
    (comp (ref "RB1_VCF")
      (value "220k")
      (footprint "eagle-import:0204_7")
      (libsource (lib "eagle-import") (part "R-EU_0204/7"))
    )
    (comp (ref "RB2")
      (value "220k")
      (footprint "eagle-import:0204_7")
      (libsource (lib "eagle-import") (part "R-EU_0204/7"))
    )
    (comp (ref "RB3_VCF")
      (value "220k")
      (footprint "eagle-import:0204_7")
      (libsource (lib "eagle-import") (part "R-EU_0204/7"))
    )
    (comp (ref "RBIAS_EXPCONV2")
      (value "47k")
      (footprint "eagle-import:0204_7")
      (libsource (lib "eagle-import") (part "R-EU_0204/7"))
    )
    (comp (ref "RC1_VCF")
      (value "91k")
      (footprint "eagle-import:0204_7")
      (libsource (lib "eagle-import") (part "R-EU_0204/7"))
    )
    (comp (ref "RC2_VCF")
      (value "91k")
      (footprint "eagle-import:0204_7")
      (libsource (lib "eagle-import") (part "R-EU_0204/7"))
    )
    (comp (ref "RC3")
      (value "91k")
      (footprint "eagle-import:0204_7")
      (libsource (lib "eagle-import") (part "R-EU_0204/7"))
    )
    (comp (ref "RC4")
      (value "91k")
      (footprint "eagle-import:0204_7")
      (libsource (lib "eagle-import") (part "R-EU_0204/7"))
    )
    (comp (ref "RCAL_1")
      (value "47k")
      (footprint "eagle-import:0204_7")
      (libsource (lib "eagle-import") (part "R-EU_0204/7"))
    )
    (comp (ref "RCAL_2")
      (value "100k")
      (footprint "eagle-import:0204_7")
      (libsource (lib "eagle-import") (part "R-EU_0204/7"))
    )
    (comp (ref "REE_2")
      (value "27k")
      (footprint "eagle-import:0204_7")
      (libsource (lib "eagle-import") (part "R-EU_0204/7"))
    )
    (comp (ref "REE_VCF")
      (value "1.5k")
      (footprint "eagle-import:0207_10")
      (libsource (lib "eagle-import") (part "R-EU_0207/10"))
    )
    (comp (ref "RF1_VCF")
      (value "100k")
      (footprint "eagle-import:0207_10")
      (libsource (lib "eagle-import") (part "R-EU_0207/10"))
    )
    (comp (ref "RF2_VCF")
      (value "100k")
      (footprint "eagle-import:0204_7")
      (libsource (lib "eagle-import") (part "R-EU_0204/7"))
    )
    (comp (ref "RF3")
      (value "100k")
      (footprint "eagle-import:0204_7")
      (libsource (lib "eagle-import") (part "R-EU_0204/7"))
    )
    (comp (ref "RF4")
      (value "100k")
      (footprint "eagle-import:0204_7")
      (libsource (lib "eagle-import") (part "R-EU_0204/7"))
    )
    (comp (ref "RIN1_MIXERA")
      (value "27k")
      (footprint "eagle-import:0204_7")
      (libsource (lib "eagle-import") (part "R-EU_0204/7"))
    )
    (comp (ref "RIN2_MIXERA")
      (value "27k")
      (footprint "eagle-import:0207_10")
      (libsource (lib "eagle-import") (part "R-EU_0207/10"))
    )
    (comp (ref "RIN2_MIXERB")
      (value "27k")
      (footprint "eagle-import:0204_7")
      (libsource (lib "eagle-import") (part "R-EU_0204/7"))
    )
    (comp (ref "RIN3_MIXERA")
      (value "27k")
      (footprint "eagle-import:0204_7")
      (libsource (lib "eagle-import") (part "R-EU_0204/7"))
    )
    (comp (ref "RIN3_MIXERB")
      (value "27k")
      (footprint "eagle-import:0204_7")
      (libsource (lib "eagle-import") (part "R-EU_0204/7"))
    )
    (comp (ref "RIN4_MIXERA")
      (value "27k")
      (footprint "eagle-import:0204_7")
      (libsource (lib "eagle-import") (part "R-EU_0204/7"))
    )
    (comp (ref "RIN4_MIXERB")
      (value "27k")
      (footprint "eagle-import:0204_7")
      (libsource (lib "eagle-import") (part "R-EU_0204/7"))
    )
    (comp (ref "RIN4_MIXERB1")
      (value "27k")
      (footprint "eagle-import:0204_7")
      (libsource (lib "eagle-import") (part "R-EU_0204/7"))
    )
    (comp (ref "RMODE_MIXERA")
      (value "8.2k")
      (footprint "eagle-import:0204_7")
      (libsource (lib "eagle-import") (part "R-EU_0204/7"))
    )
    (comp (ref "RMODE_MIXERB")
      (value "8.2k")
      (footprint "eagle-import:0204_7")
      (libsource (lib "eagle-import") (part "R-EU_0204/7"))
    )
    (comp (ref "ROUT_SUM_STG")
      (value "470")
      (footprint "eagle-import:0207_12")
      (libsource (lib "eagle-import") (part "R-EU_0207/12"))
    )
    (comp (ref "RRI_VCF")
      (value "51k")
      (footprint "eagle-import:0207_10")
      (libsource (lib "eagle-import") (part "R-EU_0207/10"))
    )
    (comp (ref "RSQU_2")
      (value "10k")
      (footprint "eagle-import:0204_7")
      (libsource (lib "eagle-import") (part "R-EU_0204/7"))
    )
    (comp (ref "RSTAB1_MIXERA")
      (value "470")
      (footprint "eagle-import:0204_7")
      (libsource (lib "eagle-import") (part "R-EU_0204/7"))
    )
    (comp (ref "RSTAB2_MIXERA")
      (value "470")
      (footprint "eagle-import:0207_10")
      (libsource (lib "eagle-import") (part "R-EU_0207/10"))
    )
    (comp (ref "RSTAB2_MIXERB")
      (value "470")
      (footprint "eagle-import:0207_10")
      (libsource (lib "eagle-import") (part "R-EU_0207/10"))
    )
    (comp (ref "RSTAB3_MIXERA")
      (value "470")
      (footprint "eagle-import:0204_7")
      (libsource (lib "eagle-import") (part "R-EU_0204/7"))
    )
    (comp (ref "RSTAB3_MIXERB")
      (value "470")
      (footprint "eagle-import:0204_7")
      (libsource (lib "eagle-import") (part "R-EU_0204/7"))
    )
    (comp (ref "RSTAB4_MIXERA")
      (value "470")
      (footprint "eagle-import:0204_7")
      (libsource (lib "eagle-import") (part "R-EU_0204/7"))
    )
    (comp (ref "RSTAB4_MIXERB")
      (value "470")
      (footprint "eagle-import:0204_7")
      (libsource (lib "eagle-import") (part "R-EU_0204/7"))
    )
    (comp (ref "RSTAB4_MIXERB1")
      (value "470")
      (footprint "eagle-import:0204_7")
      (libsource (lib "eagle-import") (part "R-EU_0204/7"))
    )
    (comp (ref "RSTAB4_MIXERB2")
      (value "470")
      (footprint "eagle-import:0204_7")
      (libsource (lib "eagle-import") (part "R-EU_0204/7"))
    )
    (comp (ref "RTEST_13700FREQ2")
      (value "27k")
      (footprint "eagle-import:0204_7")
      (libsource (lib "eagle-import") (part "R-EU_0204/7"))
    )
    (comp (ref "RTEST_LOG2")
      (value "1k")
      (footprint "eagle-import:0204_7")
      (libsource (lib "eagle-import") (part "R-EU_0204/7"))
    )
    (comp (ref "RTRI_2")
      (value "12k")
      (footprint "eagle-import:0204_7")
      (libsource (lib "eagle-import") (part "R-EU_0204/7"))
    )
    (comp (ref "R_CONV_ITOV_OUT")
      (value "33K")
      (footprint "eagle-import:0204_7")
      (libsource (lib "eagle-import") (part "R-EU_0204/7"))
    )
    (comp (ref "R_CV_FREQ1")
      (value "68k")
      (footprint "eagle-import:0204_7")
      (libsource (lib "eagle-import") (part "R-EU_0204/7"))
    )
    (comp (ref "R_CV_FREQ3")
      (value "68k")
      (footprint "eagle-import:0204_7")
      (libsource (lib "eagle-import") (part "R-EU_0204/7"))
    )
    (comp (ref "R_CV_FREQ_BIAS1")
      (value "270k")
      (footprint "eagle-import:0204_7")
      (libsource (lib "eagle-import") (part "R-EU_0204/7"))
    )
    (comp (ref "R_CV_FREQ_BIAS3")
      (value "270k")
      (footprint "eagle-import:0204_7")
      (libsource (lib "eagle-import") (part "R-EU_0204/7"))
    )
    (comp (ref "R_CV_FREQ_STAB1")
      (value "470")
      (footprint "eagle-import:0204_7")
      (libsource (lib "eagle-import") (part "R-EU_0204/7"))
    )
    (comp (ref "R_CV_FREQ_STAB3")
      (value "470")
      (footprint "eagle-import:0204_7")
      (libsource (lib "eagle-import") (part "R-EU_0204/7"))
    )
    (comp (ref "R_GAIN_VCA")
      (value "47k")
      (footprint "eagle-import:0204_7")
      (libsource (lib "eagle-import") (part "R-EU_0204/7"))
    )
    (comp (ref "R_LD2")
      (value "330")
      (footprint "eagle-import:0207_10")
      (libsource (lib "eagle-import") (part "R-US_0207/10"))
    )
    (comp (ref "R_LIM_2")
      (value "1k")
      (footprint "eagle-import:0204_7")
      (libsource (lib "eagle-import") (part "R-EU_0204/7"))
    )
    (comp (ref "R_PD_4TH_ORDER_VCF")
      (value "100k")
      (footprint "eagle-import:0204_7")
      (libsource (lib "eagle-import") (part "R-EU_0204/7"))
    )
    (comp (ref "R_PD_411_IN_PULSE1")
      (value "100k")
      (footprint "eagle-import:0207_10")
      (libsource (lib "eagle-import") (part "R-EU_0207/10"))
    )
    (comp (ref "R_PD_411_IN_SAW1")
      (value "100k")
      (footprint "eagle-import:0204_7")
      (libsource (lib "eagle-import") (part "R-EU_0204/7"))
    )
    (comp (ref "R_PD_411_IN_SYNC1")
      (value "100k")
      (footprint "eagle-import:0204_7")
      (libsource (lib "eagle-import") (part "R-EU_0204/7"))
    )
    (comp (ref "R_PD_411_IN_TRI1")
      (value "100k")
      (footprint "eagle-import:0204_7")
      (libsource (lib "eagle-import") (part "R-EU_0204/7"))
    )
    (comp (ref "R_PU_DSA")
      (value "1k")
      (footprint "eagle-import:0207_10")
      (libsource (lib "eagle-import") (part "R-US_0207/10"))
    )
    (comp (ref "R_PU_SCL")
      (value "1k")
      (footprint "eagle-import:0207_10")
      (libsource (lib "eagle-import") (part "R-US_0207/10"))
    )
    (comp (ref "R_RES_VCF")
      (value "100k")
      (footprint "eagle-import:0204_7")
      (libsource (lib "eagle-import") (part "R-EU_0204/7"))
    )
    (comp (ref "R_SYNC1")
      (value "470k")
      (footprint "eagle-import:0204_7")
      (libsource (lib "eagle-import") (part "R-EU_0204/7"))
    )
    (comp (ref "R_SYNC3")
      (value "470k")
      (footprint "eagle-import:0204_7")
      (libsource (lib "eagle-import") (part "R-EU_0204/7"))
    )
    (comp (ref "S1")
      (value "10-XX")
      (footprint "eagle-import:B3F-10XX")
      (fields (field (name "MPN") "B3F-1000"))
      (libsource (lib "eagle-import") (part "10-XX"))
    )
    (comp (ref "STM32L432KC_CONN_")
      (value "NUCLEO-F303K8")
      (footprint "eagle-import:MODULE_NUCLEO-F303K8")
      (fields (field (name "DIGI-KEY_PART_NUMBER") "497-15981-ND") (field (name "MF") "STMicroelectronics"))
      (libsource (lib "eagle-import") (part "NUCLEO-F303K8"))
    )
    (comp (ref "SUBBASS2")
      (value "HEF4027BP")
      (footprint "eagle-import:DIP254P762X420-16")
      (fields (field (name "MF") "NXP Semiconductors"))
      (libsource (lib "eagle-import") (part "HEF4027BP"))
    )
    (comp (ref "SUM_STG_C")
      (value "560p")
      (footprint "eagle-import:C075-032X103")
      (libsource (lib "eagle-import") (part "rcl_334_C-EU075-032X103"))
    )
    (comp (ref "SUM_STG_HEADER")
      (value "MA04-2")
      (footprint "eagle-import:MA04-2")
      (libsource (lib "eagle-import") (part "MA04-2"))
    )
    (comp (ref "SUM_STG_R")
      (value "27k")
      (footprint "eagle-import:0207_10")
      (libsource (lib "eagle-import") (part "R-EU_0207/10"))
    )
    (comp (ref "TP_13700_SQU2")
      (value "TESTPOINT")
      (footprint "eagle-import:TESTPOINT_63")
      (libsource (lib "eagle-import") (part "TESTPOINT"))
    )
    (comp (ref "TP_13700_TRI2")
      (value "TESTPOINT")
      (footprint "eagle-import:TESTPOINT_63")
      (libsource (lib "eagle-import") (part "TESTPOINT"))
    )
    (comp (ref "TP_CV_2")
      (value "TESTPOINT")
      (footprint "eagle-import:TESTPOINT_63")
      (libsource (lib "eagle-import") (part "TESTPOINT"))
    )
    (comp (ref "TP_PULSE1")
      (value "TESTPOINT")
      (footprint "eagle-import:TESTPOINT_63")
      (libsource (lib "eagle-import") (part "TESTPOINT"))
    )
    (comp (ref "TP_PULSE3")
      (value "TESTPOINT")
      (footprint "eagle-import:TESTPOINT_63")
      (libsource (lib "eagle-import") (part "TESTPOINT"))
    )
    (comp (ref "TP_SAW1")
      (value "TESTPOINT")
      (footprint "eagle-import:TESTPOINT_63")
      (libsource (lib "eagle-import") (part "TESTPOINT"))
    )
    (comp (ref "TP_SAW3")
      (value "TESTPOINT")
      (footprint "eagle-import:TESTPOINT_63")
      (libsource (lib "eagle-import") (part "TESTPOINT"))
    )
    (comp (ref "TP_TRI1")
      (value "TESTPOINT")
      (footprint "eagle-import:TESTPOINT_63")
      (libsource (lib "eagle-import") (part "TESTPOINT"))
    )
    (comp (ref "TP_TRI3")
      (value "TESTPOINT")
      (footprint "eagle-import:TESTPOINT_63")
      (libsource (lib "eagle-import") (part "TESTPOINT"))
    )
    (comp (ref "U1")
      (value "ANALOG_DEVICES_AD5391BSTZ-3ANALOG_DEVICES_AD5391BSTZ-3_0_0")
      (footprint "eagle-import:ANALOG_DEVICES_AD5391BSTZ-3_0")
      (fields (field (name "MF") "Analog Devices") (field (name "MPN") "AD5391BSTZ-3"))
      (libsource (lib "eagle-import") (part "ANALOG_DEVICES_AD5391BSTZ-3ANALOG_DEVICES_AD5391BSTZ-3_0_0"))
    )
    (comp (ref "VCA")
      (value "LM13700N")
      (footprint "eagle-import:DIL16")
      (libsource (lib "eagle-import") (part "LM13700N"))
    )
    (comp (ref "VCF")
      (value "AS3320")
      (footprint "eagle-import:DIL18")
      (libsource (lib "eagle-import") (part "AS3320"))
    )
    (comp (ref "VCF_ANALOG_SW")
      (value "DG413DJN")
      (footprint "eagle-import:DIL16")
      (libsource (lib "eagle-import") (part "DG413DJN"))
    )
    (comp (ref "VCF_JUMPER")
      (value "MA04-1")
      (footprint "eagle-import:MA04-1")
      (libsource (lib "eagle-import") (part "MA04-1"))
    )
    (comp (ref "VCO2")
      (value "LM13700N")
      (footprint "eagle-import:DIL16")
      (libsource (lib "eagle-import") (part "LM13700N"))
    )
  )
  (nets
    (net (code "1") (name "+15V") (class "Default")
      (node (ref "3") (pin "13") (pinfunction "VDD_13") (pintype "power_in"))
      (node (ref "3340A") (pin "16") (pinfunction "VCC_16") (pintype "bidirectional"))
      (node (ref "3340B") (pin "16") (pinfunction "VCC_16") (pintype "bidirectional"))
      (node (ref "C+15VPOL_VCF") (pin "2") (pinfunction "2_2") (pintype "passive"))
      (node (ref "C+15V_SUM_STG") (pin "2") (pinfunction "2_2") (pintype "passive"))
      (node (ref "C+15V_VCF") (pin "2") (pinfunction "2_2") (pintype "passive"))
      (node (ref "CDEC+15V6") (pin "1") (pinfunction "1_1") (pintype "passive"))
      (node (ref "CDEC+15V7") (pin "1") (pinfunction "1_1") (pintype "passive"))
      (node (ref "CDEC+15VPOL_MIXERB") (pin "2") (pinfunction "2_2") (pintype "passive"))
      (node (ref "CDEC+15V_MIXERB") (pin "2") (pinfunction "2_2") (pintype "passive"))
      (node (ref "CDEC_3340A2") (pin "2") (pinfunction "2_2") (pintype "passive"))
      (node (ref "CDEC_3340A3") (pin "2") (pinfunction "2_2") (pintype "passive"))
      (node (ref "CDEC_3340A6") (pin "2") (pinfunction "2_2") (pintype "passive"))
      (node (ref "CDEC_3340A7") (pin "2") (pinfunction "2_2") (pintype "passive"))
      (node (ref "CONV_ITOV_OUT") (pin "7") (pinfunction "V+_7") (pintype "power_in"))
      (node (ref "EXPCONV2") (pin "7") (pinfunction "V+_7") (pintype "power_in"))
      (node (ref "MIXER_A") (pin "16") (pinfunction "V+_16") (pintype "bidirectional"))
      (node (ref "MIXER_B") (pin "16") (pinfunction "V+_16") (pintype "bidirectional"))
      (node (ref "OPAMP_SUM_STG") (pin "7") (pinfunction "V+_7") (pintype "power_in"))
      (node (ref "R2_PWM1") (pin "2") (pinfunction "2_2") (pintype "passive"))
      (node (ref "R2_PWM3") (pin "2") (pinfunction "2_2") (pintype "passive"))
      (node (ref "R4_VCA") (pin "1") (pinfunction "1_1") (pintype "passive"))
      (node (ref "R8_1") (pin "2") (pinfunction "2_2") (pintype "passive"))
      (node (ref "R8_3") (pin "2") (pinfunction "2_2") (pintype "passive"))
      (node (ref "RMODE_MIXERA") (pin "1") (pinfunction "1_1") (pintype "passive"))
      (node (ref "RMODE_MIXERB") (pin "1") (pinfunction "1_1") (pintype "passive"))
      (node (ref "R_CV_FREQ_BIAS1") (pin "2") (pinfunction "2_2") (pintype "passive"))
      (node (ref "R_CV_FREQ_BIAS3") (pin "2") (pinfunction "2_2") (pintype "passive"))
      (node (ref "VCA") (pin "11") (pinfunction "V+_11") (pintype "power_in"))
      (node (ref "VCF") (pin "14") (pinfunction "V+_14") (pintype "bidirectional"))
      (node (ref "VCF_ANALOG_SW") (pin "13") (pinfunction "V+_13") (pintype "power_in"))
      (node (ref "VCO2") (pin "11") (pinfunction "V+_11") (pintype "power_in"))
    )
    (net (code "2") (name "-15V") (class "Default")
      (node (ref "3") (pin "4") (pinfunction "VSS_4") (pintype "power_in"))
      (node (ref "C-15V_SUM_STG") (pin "1") (pinfunction "1_1") (pintype "passive"))
      (node (ref "CDEC-15V6") (pin "2") (pinfunction "2_2") (pintype "passive"))
      (node (ref "CDEC-15V7") (pin "2") (pinfunction "2_2") (pintype "passive"))
      (node (ref "CDEC-15VPOL_MIXERB") (pin "1") (pinfunction "1_1") (pintype "passive"))
      (node (ref "CDEC-15V_MIXERB") (pin "1") (pinfunction "1_1") (pintype "passive"))
      (node (ref "CONV_ITOV_OUT") (pin "4") (pinfunction "V-_4") (pintype "power_in"))
      (node (ref "EXPCONV2") (pin "4") (pinfunction "V-_4") (pintype "power_in"))
      (node (ref "MIXER_A") (pin "9") (pinfunction "V-_9") (pintype "bidirectional"))
      (node (ref "MIXER_B") (pin "9") (pinfunction "V-_9") (pintype "bidirectional"))
      (node (ref "OPAMP_SUM_STG") (pin "4") (pinfunction "V-_4") (pintype "power_in"))
      (node (ref "R3_1") (pin "1") (pinfunction "1_1") (pintype "passive"))
      (node (ref "R3_3") (pin "1") (pinfunction "1_1") (pintype "passive"))
      (node (ref "RB1_VCF") (pin "1") (pinfunction "1_1") (pintype "passive"))
      (node (ref "RB2") (pin "1") (pinfunction "1_1") (pintype "passive"))
      (node (ref "RB3_VCF") (pin "1") (pinfunction "1_1") (pintype "passive"))
      (node (ref "RBIAS_EXPCONV2") (pin "1") (pinfunction "1_1") (pintype "passive"))
      (node (ref "REE_VCF") (pin "1") (pinfunction "1_1") (pintype "passive"))
      (node (ref "RSQU_2") (pin "1") (pinfunction "1_1") (pintype "passive"))
      (node (ref "RTRI_2") (pin "1") (pinfunction "1_1") (pintype "passive"))
      (node (ref "VCF_ANALOG_SW") (pin "4") (pinfunction "V-_4") (pintype "power_in"))
      (node (ref "VCO2") (pin "6") (pinfunction "V-_6") (pintype "power_in"))
    )
    (net (code "3") (name "3V3") (class "Default")
      (node (ref "R_PU_DSA") (pin "2") (pinfunction "2_2") (pintype "passive"))
      (node (ref "R_PU_SCL") (pin "2") (pinfunction "2_2") (pintype "passive"))
    )
    (net (code "4") (name "5V") (class "Default")
      (node (ref "3") (pin "12") (pinfunction "VL_12") (pintype "power_in"))
      (node (ref "C5VPOL_VCF") (pin "1") (pinfunction "1_1") (pintype "passive"))
      (node (ref "C5V_VCF") (pin "1") (pinfunction "1_1") (pintype "passive"))
      (node (ref "CDEC_411B6") (pin "1") (pinfunction "1_1") (pintype "passive"))
      (node (ref "CDEC_411B7") (pin "1") (pinfunction "1_1") (pintype "passive"))
      (node (ref "CDEC_5V1") (pin "1") (pinfunction "1_1") (pintype "passive"))
      (node (ref "CDEC_5V4") (pin "1") (pinfunction "1_1") (pintype "passive"))
      (node (ref "CDEC_AVDD1") (pin "2") (pinfunction "2_2") (pintype "passive"))
      (node (ref "CDEC_AVDD1_100N") (pin "2") (pinfunction "2_2") (pintype "passive"))
      (node (ref "CDEC_AVDD2") (pin "2") (pinfunction "2_2") (pintype "passive"))
      (node (ref "CDEC_AVDD2_100N") (pin "2") (pinfunction "2_2") (pintype "passive"))
      (node (ref "CDEC_DVDD1") (pin "2") (pinfunction "2_2") (pintype "passive"))
      (node (ref "CDEC_DVDD2") (pin "2") (pinfunction "2_2") (pintype "passive"))
      (node (ref "IC_EEPROM") (pin "2") (pinfunction "A1_2") (pintype "input"))
      (node (ref "IC_EEPROM") (pin "3") (pinfunction "A2_3") (pintype "input"))
      (node (ref "IC_EEPROM") (pin "8") (pinfunction "VCC_8") (pintype "power_in"))
      (node (ref "R1_8") (pin "1") (pinfunction "1_1") (pintype "passive"))
      (node (ref "R3_EXPCONV2") (pin "2") (pinfunction "2_2") (pintype "passive"))
      (node (ref "R_PD_411_IN_SAW1") (pin "2") (pinfunction "2_2") (pintype "passive"))
      (node (ref "STM32L432KC_CONN_") (pin "4.1") (pinfunction "VIN_4.1") (pintype "bidirectional"))
      (node (ref "SUBBASS2") (pin "11") (pinfunction "1K_11") (pintype "input"))
      (node (ref "SUBBASS2") (pin "16") (pinfunction "VDD_16") (pintype "power_in"))
      (node (ref "U1") (pin "1") (pinfunction "~{CLR}_1") (pintype "input"))
      (node (ref "U1") (pin "32") (pinfunction "AVDD_2_32") (pintype "power_in"))
      (node (ref "U1") (pin "42") (pinfunction "~{I2C}_42") (pintype "input"))
      (node (ref "U1") (pin "44") (pinfunction "1_DVDD_44") (pintype "power_in"))
      (node (ref "U1") (pin "45") (pinfunction "2_DVDD_45") (pintype "power_in"))
      (node (ref "U1") (pin "47") (pinfunction "3_DVDD_47") (pintype "power_in"))
      (node (ref "U1") (pin "8") (pinfunction "AVDD_1_8") (pintype "power_in"))
      (node (ref "VCF_ANALOG_SW") (pin "12") (pinfunction "VL_12") (pintype "input"))
    )
    (net (code "5") (name "411_IN_PULSE") (class "Default")
      (node (ref "3") (pin "8") (pinfunction "IN_8") (pintype "input"))
      (node (ref "R_PD_411_IN_PULSE1") (pin "2") (pinfunction "2_2") (pintype "passive"))
      (node (ref "STM32L432KC_CONN_") (pin "3.10") (pinfunction "PF0_3.10") (pintype "bidirectional"))
    )
    (net (code "6") (name "411_IN_SAW") (class "Default")
      (node (ref "3") (pin "9") (pinfunction "IN_9") (pintype "input"))
      (node (ref "R_PD_411_IN_SAW1") (pin "1") (pinfunction "1_1") (pintype "passive"))
      (node (ref "STM32L432KC_CONN_") (pin "3.11") (pinfunction "PF1_3.11") (pintype "bidirectional"))
    )
    (net (code "7") (name "411_IN_SYNC") (class "Default")
      (node (ref "3") (pin "16") (pinfunction "IN_16") (pintype "input"))
      (node (ref "R_PD_411_IN_SYNC1") (pin "1") (pinfunction "1_1") (pintype "passive"))
      (node (ref "STM32L432KC_CONN_") (pin "3.6") (pinfunction "PB0_3.6") (pintype "bidirectional"))
    )
    (net (code "8") (name "411_IN_TRI") (class "Default")
      (node (ref "3") (pin "1") (pinfunction "IN_1") (pintype "input"))
      (node (ref "R_PD_411_IN_TRI1") (pin "1") (pinfunction "1_1") (pintype "passive"))
      (node (ref "STM32L432KC_CONN_") (pin "3.9") (pinfunction "PB1_3.9") (pintype "bidirectional"))
    )
    (net (code "9") (name "2164_IN1_MIXA") (class "Default")
      (node (ref "MIXER_A") (pin "2") (pinfunction "I_IN_2") (pintype "bidirectional"))
      (node (ref "RIN1_MIXERA") (pin "1") (pinfunction "1_1") (pintype "passive"))
      (node (ref "RSTAB1_MIXERA") (pin "1") (pinfunction "1_1") (pintype "passive"))
    )
    (net (code "10") (name "2164_IN2_MIXA") (class "Default")
      (node (ref "MIXER_A") (pin "7") (pinfunction "I_IN_7") (pintype "bidirectional"))
      (node (ref "RIN2_MIXERA") (pin "1") (pinfunction "1_1") (pintype "passive"))
      (node (ref "RSTAB2_MIXERA") (pin "1") (pinfunction "1_1") (pintype "passive"))
    )
    (net (code "11") (name "2164_IN2_MIXB") (class "Default")
      (node (ref "MIXER_B") (pin "7") (pinfunction "I_IN_7") (pintype "bidirectional"))
      (node (ref "RIN2_MIXERB") (pin "1") (pinfunction "1_1") (pintype "passive"))
      (node (ref "RSTAB2_MIXERB") (pin "1") (pinfunction "1_1") (pintype "passive"))
    )
    (net (code "12") (name "2164_IN3_MIXA") (class "Default")
      (node (ref "MIXER_A") (pin "10") (pinfunction "I_IN_10") (pintype "bidirectional"))
      (node (ref "RIN3_MIXERA") (pin "1") (pinfunction "1_1") (pintype "passive"))
      (node (ref "RSTAB3_MIXERA") (pin "1") (pinfunction "1_1") (pintype "passive"))
    )
    (net (code "13") (name "2164_IN3_MIXB") (class "Default")
      (node (ref "MIXER_B") (pin "10") (pinfunction "I_IN_10") (pintype "bidirectional"))
      (node (ref "RIN3_MIXERB") (pin "1") (pinfunction "1_1") (pintype "passive"))
      (node (ref "RSTAB3_MIXERB") (pin "1") (pinfunction "1_1") (pintype "passive"))
    )
    (net (code "14") (name "2164_IN4_MIXA") (class "Default")
      (node (ref "MIXER_A") (pin "15") (pinfunction "I_IN_15") (pintype "bidirectional"))
      (node (ref "RIN4_MIXERA") (pin "1") (pinfunction "1_1") (pintype "passive"))
      (node (ref "RSTAB4_MIXERA") (pin "1") (pinfunction "1_1") (pintype "passive"))
    )
    (net (code "15") (name "2164_IN4_MIXB") (class "Default")
      (node (ref "MIXER_B") (pin "15") (pinfunction "I_IN_15") (pintype "bidirectional"))
      (node (ref "RIN4_MIXERB") (pin "1") (pinfunction "1_1") (pintype "passive"))
      (node (ref "RSTAB4_MIXERB") (pin "1") (pinfunction "1_1") (pintype "passive"))
    )
    (net (code "16") (name "2164_MODE_MIXA") (class "Default")
      (node (ref "MIXER_A") (pin "1") (pinfunction "MODE_1") (pintype "bidirectional"))
      (node (ref "RMODE_MIXERA") (pin "2") (pinfunction "2_2") (pintype "passive"))
    )
    (net (code "17") (name "2164_MODE_MIXB") (class "Default")
      (node (ref "MIXER_B") (pin "1") (pinfunction "MODE_1") (pintype "bidirectional"))
      (node (ref "RMODE_MIXERB") (pin "2") (pinfunction "2_2") (pintype "passive"))
    )
    (net (code "18") (name "2164_OUT2_MIXA") (class "Default")
      (node (ref "JP_MIXER_A") (pin "2") (pinfunction "2_2") (pintype "passive"))
      (node (ref "MIXER_A") (pin "5") (pinfunction "I_OUT_5") (pintype "bidirectional"))
    )
    (net (code "19") (name "2164_OUT2_MIXB") (class "Default")
      (node (ref "JP_MIXER_B") (pin "4") (pinfunction "4_4") (pintype "passive"))
      (node (ref "MIXER_B") (pin "5") (pinfunction "I_OUT_5") (pintype "bidirectional"))
    )
    (net (code "20") (name "2164_OUT3_MIXA") (class "Default")
      (node (ref "JP_MIXER_A") (pin "6") (pinfunction "6_6") (pintype "passive"))
      (node (ref "MIXER_A") (pin "12") (pinfunction "I_OUT_12") (pintype "bidirectional"))
    )
    (net (code "21") (name "2164_OUT4_MIXA") (class "Default")
      (node (ref "JP_MIXER_A") (pin "8") (pinfunction "8_8") (pintype "passive"))
      (node (ref "MIXER_A") (pin "13") (pinfunction "I_OUT_13") (pintype "bidirectional"))
    )
    (net (code "22") (name "2164_OUT4_MIXB") (class "Default")
      (node (ref "JP_MIXER_B") (pin "6") (pinfunction "6_6") (pintype "passive"))
      (node (ref "MIXER_B") (pin "13") (pinfunction "I_OUT_13") (pintype "bidirectional"))
    )
    (net (code "23") (name "AGND") (class "Default")
      (node (ref "3") (pin "5") (pinfunction "GND_5") (pintype "power_in"))
      (node (ref "3340A") (pin "12") (pinfunction "GND_12") (pintype "bidirectional"))
      (node (ref "3340B") (pin "12") (pinfunction "GND_12") (pintype "bidirectional"))
      (node (ref "C+15VPOL_VCF") (pin "1") (pinfunction "1_1") (pintype "passive"))
      (node (ref "C+15V_SUM_STG") (pin "1") (pinfunction "1_1") (pintype "passive"))
      (node (ref "C+15V_VCF") (pin "1") (pinfunction "1_1") (pintype "passive"))
      (node (ref "C-15VPOL_VCF") (pin "2") (pinfunction "2_2") (pintype "passive"))
      (node (ref "C-15V_SUM_STG") (pin "2") (pinfunction "2_2") (pintype "passive"))
      (node (ref "C-15V_VCF") (pin "2") (pinfunction "2_2") (pintype "passive"))
      (node (ref "C10") (pin "1") (pinfunction "1_1") (pintype "passive"))
      (node (ref "C1_VCA") (pin "2") (pinfunction "2_2") (pintype "passive"))
      (node (ref "C2_SYNC1") (pin "1") (pinfunction "1_1") (pintype "passive"))
      (node (ref "C2_SYNC3") (pin "1") (pinfunction "1_1") (pintype "passive"))
      (node (ref "C3") (pin "1") (pinfunction "1_1") (pintype "passive"))
      (node (ref "C4") (pin "1") (pinfunction "1_1") (pintype "passive"))
      (node (ref "C4_1") (pin "2") (pinfunction "2_2") (pintype "passive"))
      (node (ref "C4_3") (pin "2") (pinfunction "2_2") (pintype "passive"))
      (node (ref "C5") (pin "1") (pinfunction "1_1") (pintype "passive"))
      (node (ref "C5VPOL_VCF") (pin "2") (pinfunction "2_2") (pintype "passive"))
      (node (ref "C5V_VCF") (pin "2") (pinfunction "2_2") (pintype "passive"))
      (node (ref "CDEC+15V6") (pin "2") (pinfunction "2_2") (pintype "passive"))
      (node (ref "CDEC+15V7") (pin "2") (pinfunction "2_2") (pintype "passive"))
      (node (ref "CDEC+15VPOL_MIXERB") (pin "1") (pinfunction "1_1") (pintype "passive"))
      (node (ref "CDEC+15V_MIXERB") (pin "1") (pinfunction "1_1") (pintype "passive"))
      (node (ref "CDEC-15V6") (pin "1") (pinfunction "1_1") (pintype "passive"))
      (node (ref "CDEC-15V7") (pin "1") (pinfunction "1_1") (pintype "passive"))
      (node (ref "CDEC-15VPOL_MIXERB") (pin "2") (pinfunction "2_2") (pintype "passive"))
      (node (ref "CDEC-15V_MIXERB") (pin "2") (pinfunction "2_2") (pintype "passive"))
      (node (ref "CDEC_3340A2") (pin "1") (pinfunction "1_1") (pintype "passive"))
      (node (ref "CDEC_3340A3") (pin "1") (pinfunction "1_1") (pintype "passive"))
      (node (ref "CDEC_3340A6") (pin "1") (pinfunction "1_1") (pintype "passive"))
      (node (ref "CDEC_3340A7") (pin "1") (pinfunction "1_1") (pintype "passive"))
      (node (ref "CDEC_3340B2") (pin "1") (pinfunction "1_1") (pintype "passive"))
      (node (ref "CDEC_3340B3") (pin "1") (pinfunction "1_1") (pintype "passive"))
      (node (ref "CDEC_3340B6") (pin "1") (pinfunction "1_1") (pintype "passive"))
      (node (ref "CDEC_3340B7") (pin "1") (pinfunction "1_1") (pintype "passive"))
      (node (ref "CDEC_411B6") (pin "2") (pinfunction "2_2") (pintype "passive"))
      (node (ref "CDEC_411B7") (pin "2") (pinfunction "2_2") (pintype "passive"))
      (node (ref "CDEC_5V1") (pin "2") (pinfunction "2_2") (pintype "passive"))
      (node (ref "CDEC_5V4") (pin "2") (pinfunction "2_2") (pintype "passive"))
      (node (ref "CDEC_AVDD1") (pin "1") (pinfunction "1_1") (pintype "passive"))
      (node (ref "CDEC_AVDD1_100N") (pin "1") (pinfunction "1_1") (pintype "passive"))
      (node (ref "CDEC_AVDD2") (pin "1") (pinfunction "1_1") (pintype "passive"))
      (node (ref "CDEC_AVDD2_100N") (pin "1") (pinfunction "1_1") (pintype "passive"))
      (node (ref "CDEC_DVDD1") (pin "1") (pinfunction "1_1") (pintype "passive"))
      (node (ref "CDEC_DVDD2") (pin "1") (pinfunction "1_1") (pintype "passive"))
      (node (ref "CDEC_VREF") (pin "2") (pinfunction "2_2") (pintype "passive"))
      (node (ref "CF_2") (pin "1") (pinfunction "1_1") (pintype "passive"))
      (node (ref "CONN_UART_RPI") (pin "1") (pinfunction "1_1") (pintype "passive"))
      (node (ref "CONV_ITOV_OUT") (pin "3") (pinfunction "+IN_3") (pintype "input"))
      (node (ref "CSTAB1_MIXERA") (pin "1") (pinfunction "1_1") (pintype "passive"))
      (node (ref "CSTAB2_MIXERA") (pin "1") (pinfunction "1_1") (pintype "passive"))
      (node (ref "CSTAB2_MIXERB") (pin "1") (pinfunction "1_1") (pintype "passive"))
      (node (ref "CSTAB3") (pin "1") (pinfunction "1_1") (pintype "passive"))
      (node (ref "CSTAB3_MIXERA") (pin "1") (pinfunction "1_1") (pintype "passive"))
      (node (ref "CSTAB3_MIXERB") (pin "1") (pinfunction "1_1") (pintype "passive"))
      (node (ref "CSTAB4_MIXERA") (pin "1") (pinfunction "1_1") (pintype "passive"))
      (node (ref "CSTAB8") (pin "1") (pinfunction "1_1") (pintype "passive"))
      (node (ref "C_1") (pin "1") (pinfunction "1_1") (pintype "passive"))
      (node (ref "C_3") (pin "1") (pinfunction "1_1") (pintype "passive"))
      (node (ref "C_CV_FREQ_STAB1") (pin "1") (pinfunction "1_1") (pintype "passive"))
      (node (ref "C_CV_FREQ_STAB3") (pin "1") (pinfunction "1_1") (pintype "passive"))
      (node (ref "C_SW1") (pin "2") (pinfunction "2_2") (pintype "passive"))
      (node (ref "EXPCONV2") (pin "3") (pinfunction "+IN_3") (pintype "input"))
      (node (ref "IC_EEPROM") (pin "1") (pinfunction "A0_1") (pintype "input"))
      (node (ref "IC_EEPROM") (pin "4") (pinfunction "GND_4") (pintype "power_in"))
      (node (ref "IC_EEPROM") (pin "7") (pinfunction "WP_7") (pintype "input"))
      (node (ref "LD2_RED") (pin "K") (pinfunction "C_K") (pintype "passive"))
      (node (ref "MIXER_A") (pin "8") (pinfunction "GND_8") (pintype "bidirectional"))
      (node (ref "MIXER_B") (pin "8") (pinfunction "GND_8") (pintype "bidirectional"))
      (node (ref "OUT") (pin "2") (pinfunction "2_2") (pintype "passive"))
      (node (ref "POT_SUM_STG") (pin "1") (pinfunction "A_1") (pintype "passive"))
      (node (ref "R11_1") (pin "2") (pinfunction "2_2") (pintype "passive"))
      (node (ref "R11_3") (pin "2") (pinfunction "2_2") (pintype "passive"))
      (node (ref "R1_7") (pin "1") (pinfunction "1_1") (pintype "passive"))
      (node (ref "R1_PWM1") (pin "2") (pinfunction "2_2") (pintype "passive"))
      (node (ref "R1_PWM3") (pin "2") (pinfunction "2_2") (pintype "passive"))
      (node (ref "R1_VCF") (pin "2") (pinfunction "2_2") (pintype "passive"))
      (node (ref "R2_7") (pin "1") (pinfunction "1_1") (pintype "passive"))
      (node (ref "R2_8") (pin "2") (pinfunction "2_2") (pintype "passive"))
      (node (ref "R2_EXPCONV2") (pin "2") (pinfunction "2_2") (pintype "passive"))
      (node (ref "R2_VCA") (pin "1") (pinfunction "1_1") (pintype "passive"))
      (node (ref "R3_4") (pin "1") (pinfunction "1_1") (pintype "passive"))
      (node (ref "R3_VCA") (pin "2") (pinfunction "2_2") (pintype "passive"))
      (node (ref "R4_EXPCONV2") (pin "2") (pinfunction "2_2") (pintype "passive"))
      (node (ref "R5_1") (pin "2") (pinfunction "2_2") (pintype "passive"))
      (node (ref "R5_3") (pin "2") (pinfunction "2_2") (pintype "passive"))
      (node (ref "RA_2") (pin "1") (pinfunction "1_1") (pintype "passive"))
      (node (ref "RCAL_2") (pin "2") (pinfunction "2_2") (pintype "passive"))
      (node (ref "REE_2") (pin "2") (pinfunction "2_2") (pintype "passive"))
      (node (ref "RSTAB4_MIXERB1") (pin "1") (pinfunction "1_1") (pintype "passive"))
      (node (ref "RTEST_LOG2") (pin "2") (pinfunction "2_2") (pintype "passive"))
      (node (ref "R_PD_411_IN_PULSE1") (pin "1") (pinfunction "1_1") (pintype "passive"))
      (node (ref "R_PD_411_IN_SYNC1") (pin "2") (pinfunction "2_2") (pintype "passive"))
      (node (ref "R_PD_411_IN_TRI1") (pin "2") (pinfunction "2_2") (pintype "passive"))
      (node (ref "R_PD_4TH_ORDER_VCF") (pin "1") (pinfunction "1_1") (pintype "passive"))
      (node (ref "R_SYNC1") (pin "1") (pinfunction "1_1") (pintype "passive"))
      (node (ref "R_SYNC3") (pin "1") (pinfunction "1_1") (pintype "passive"))
      (node (ref "S1") (pin "1") (pinfunction "S_1") (pintype "passive"))
      (node (ref "S1") (pin "2") (pinfunction "S1_2") (pintype "passive"))
      (node (ref "STM32L432KC_CONN_") (pin "3.4") (pinfunction "GND_3.4") (pintype "bidirectional"))
      (node (ref "STM32L432KC_CONN_") (pin "4.2") (pinfunction "GND_4.2") (pintype "bidirectional"))
      (node (ref "SUBBASS2") (pin "12") (pinfunction "1CD_12") (pintype "input"))
      (node (ref "SUBBASS2") (pin "8") (pinfunction "VSS_8") (pintype "passive"))
      (node (ref "SUBBASS2") (pin "9") (pinfunction "1SD_9") (pintype "input"))
      (node (ref "U1") (pin "14") (pinfunction "AGND_1_14") (pintype "power_in"))
      (node (ref "U1") (pin "26") (pinfunction "DAC_GND_2_26") (pintype "power_in"))
      (node (ref "U1") (pin "27") (pinfunction "SIGNAL_GND_2_27") (pintype "power_in"))
      (node (ref "U1") (pin "31") (pinfunction "AGND_2_31") (pintype "power_in"))
      (node (ref "U1") (pin "4") (pinfunction "REF_GND_4") (pintype "power_in"))
      (node (ref "U1") (pin "40") (pinfunction "DCEN/AD1_40") (pintype "input"))
      (node (ref "U1") (pin "41") (pinfunction "PD_41") (pintype "input"))
      (node (ref "U1") (pin "43") (pinfunction "1_DGND_43") (pintype "power_in"))
      (node (ref "U1") (pin "46") (pinfunction "2_DGND_46") (pintype "power_in"))
      (node (ref "U1") (pin "52") (pinfunction "3_DGND_52") (pintype "power_in"))
      (node (ref "U1") (pin "6") (pinfunction "SIGNAL_GND_1_6") (pintype "power_in"))
      (node (ref "U1") (pin "7") (pinfunction "DAC_GND_1_7") (pintype "power_in"))
      (node (ref "VCA") (pin "6") (pinfunction "V-_6") (pintype "power_in"))
      (node (ref "VCF") (pin "3") (pinfunction "GND_3") (pintype "bidirectional"))
      (node (ref "VCF_ANALOG_SW") (pin "5") (pinfunction "GND_5") (pintype "power_in"))
      (node (ref "VCO2") (pin "4") (pinfunction "IN_N_4") (pintype "input"))
    )
    (net (code "24") (name "BIAS_4027_VCO13700") (class "Default")
      (node (ref "CIN_2") (pin "1") (pinfunction "1_1") (pintype "passive"))
      (node (ref "D_2") (pin "A") (pinfunction "A_A") (pintype "passive"))
      (node (ref "R1_8") (pin "2") (pinfunction "2_2") (pintype "passive"))
      (node (ref "R2_8") (pin "1") (pinfunction "1_1") (pintype "passive"))
    )
    (net (code "25") (name "BIAS_VCA") (class "Default")
      (node (ref "C1_VCA") (pin "1") (pinfunction "1_1") (pintype "passive"))
      (node (ref "C2_VCA") (pin "1") (pinfunction "1_1") (pintype "passive"))
      (node (ref "OPAMP_SUM_STG") (pin "3") (pinfunction "+IN_3") (pintype "input"))
      (node (ref "R3_VCA") (pin "1") (pinfunction "1_1") (pintype "passive"))
      (node (ref "R4_VCA") (pin "2") (pinfunction "2_2") (pintype "passive"))
      (node (ref "R5_VCA") (pin "1") (pinfunction "1_1") (pintype "passive"))
      (node (ref "VCA") (pin "3") (pinfunction "IN_P_3") (pintype "input"))
    )
    (net (code "26") (name "CALIB_3340A") (class "Default")
      (node (ref "R5_3") (pin "1") (pinfunction "1_1") (pintype "passive"))
      (node (ref "R6_3") (pin "1") (pinfunction "1_1") (pintype "passive"))
      (node (ref "STM32L432KC_CONN_") (pin "3.12") (pinfunction "PA8_3.12") (pintype "bidirectional"))
    )
    (net (code "27") (name "CALIB_3340B") (class "Default")
      (node (ref "R5_1") (pin "1") (pinfunction "1_1") (pintype "passive"))
      (node (ref "R6_1") (pin "1") (pinfunction "1_1") (pintype "passive"))
      (node (ref "STM32L432KC_CONN_") (pin "3.1") (pinfunction "PA9_3.1") (pintype "bidirectional"))
    )
    (net (code "28") (name "CALIB_13700") (class "Default")
      (node (ref "RCAL_1") (pin "2") (pinfunction "2_2") (pintype "passive"))
      (node (ref "RCAL_2") (pin "1") (pinfunction "1_1") (pintype "passive"))
      (node (ref "STM32L432KC_CONN_") (pin "3.2") (pinfunction "PA10_3.2") (pintype "bidirectional"))
    )
    (net (code "29") (name "CAP1_VCF") (class "Default")
      (node (ref "C3") (pin "2") (pinfunction "2_2") (pintype "passive"))
      (node (ref "VCF") (pin "5") (pinfunction "CAP_5") (pintype "bidirectional"))
    )
    (net (code "30") (name "CAP2_VCF") (class "Default")
      (node (ref "C5") (pin "2") (pinfunction "2_2") (pintype "passive"))
      (node (ref "VCF") (pin "4") (pinfunction "CAP_4") (pintype "bidirectional"))
    )
    (net (code "31") (name "CAP3_VCF") (class "Default")
      (node (ref "C4") (pin "2") (pinfunction "2_2") (pintype "passive"))
      (node (ref "VCF") (pin "16") (pinfunction "CAP_16") (pintype "bidirectional"))
    )
    (net (code "32") (name "CAP4_VCF") (class "Default")
      (node (ref "C10") (pin "2") (pinfunction "2_2") (pintype "passive"))
      (node (ref "VCF") (pin "11") (pinfunction "CAP_11") (pintype "bidirectional"))
    )
    (net (code "33") (name "CV_CUTOFF") (class "Default")
      (node (ref "R2_VCF") (pin "2") (pinfunction "2_2") (pintype "passive"))
      (node (ref "U1") (pin "28") (pinfunction "VOUT_13_28") (pintype "tri_state"))
    )
    (net (code "34") (name "CV_FREQ_3340A") (class "Default")
      (node (ref "JP_FMLIN_VCO3340B1") (pin "1") (pinfunction "1_1") (pintype "passive"))
      (node (ref "R_CV_FREQ3") (pin "2") (pinfunction "2_2") (pintype "passive"))
      (node (ref "U1") (pin "12") (pinfunction "VOUT_3_12") (pintype "tri_state"))
    )
    (net (code "35") (name "CV_FREQ_3340B") (class "Default")
      (node (ref "R_CV_FREQ1") (pin "2") (pinfunction "2_2") (pintype "passive"))
      (node (ref "U1") (pin "9") (pinfunction "VOUT_0_9") (pintype "tri_state"))
    )
    (net (code "36") (name "CV_FREQ_13700") (class "Default")
      (node (ref "R1_EXPCONV2") (pin "2") (pinfunction "2_2") (pintype "passive"))
      (node (ref "TP_CV_2") (pin "P$1") (pinfunction "P$1_P$1") (pintype "passive"))
      (node (ref "U1") (pin "11") (pinfunction "VOUT_2_11") (pintype "tri_state"))
    )
    (net (code "37") (name "CV_PWM_3340A") (class "Default")
      (node (ref "3340A") (pin "5") (pinfunction "PWM_CTRL_5") (pintype "bidirectional"))
      (node (ref "R1_PWM3") (pin "1") (pinfunction "1_1") (pintype "passive"))
      (node (ref "R2_PWM3") (pin "1") (pinfunction "1_1") (pintype "passive"))
      (node (ref "U1") (pin "13") (pinfunction "VOUT_4_13") (pintype "tri_state"))
    )
    (net (code "38") (name "CV_PWM_3340B") (class "Default")
      (node (ref "3340B") (pin "5") (pinfunction "PWM_CTRL_5") (pintype "bidirectional"))
      (node (ref "R1_PWM1") (pin "1") (pinfunction "1_1") (pintype "passive"))
      (node (ref "R2_PWM1") (pin "1") (pinfunction "1_1") (pintype "passive"))
      (node (ref "U1") (pin "10") (pinfunction "VOUT_1_10") (pintype "tri_state"))
    )
    (net (code "39") (name "CV_RES") (class "Default")
      (node (ref "R_RES_VCF") (pin "2") (pinfunction "2_2") (pintype "passive"))
      (node (ref "U1") (pin "29") (pinfunction "VOUT_14_29") (pintype "tri_state"))
    )
    (net (code "40") (name "CV_VCA") (class "Default")
      (node (ref "R_GAIN_VCA") (pin "1") (pinfunction "1_1") (pintype "passive"))
      (node (ref "U1") (pin "30") (pinfunction "VOUT_15_30") (pintype "tri_state"))
    )
    (net (code "41") (name "DAC_LDAC") (class "Default")
      (node (ref "STM32L432KC_CONN_") (pin "4.8") (pinfunction "PA5_4.8") (pintype "bidirectional"))
      (node (ref "U1") (pin "39") (pinfunction "~{LDAC}_39") (pintype "input"))
    )
    (net (code "42") (name "DAC_SYNC") (class "Default")
      (node (ref "STM32L432KC_CONN_") (pin "4.10") (pinfunction "PA3_4.10") (pintype "bidirectional"))
      (node (ref "U1") (pin "51") (pinfunction "~{SYNC}/AD0_51") (pintype "input"))
    )
    (net (code "43") (name "FM_ENTREE_13700_VCO13700") (class "Default")
      (node (ref "HEADER_EXPCONV2") (pin "3") (pinfunction "3_3") (pintype "passive"))
      (node (ref "RTEST_13700FREQ2") (pin "2") (pinfunction "2_2") (pintype "passive"))
      (node (ref "VCO2") (pin "1") (pinfunction "I_BIAS_1") (pintype "input"))
    )
    (net (code "44") (name "FREQ_CTRL_VCOA") (class "Default")
      (node (ref "3340A") (pin "15") (pinfunction "FREQ_CTRL_15") (pintype "bidirectional"))
      (node (ref "R_CV_FREQ3") (pin "1") (pinfunction "1_1") (pintype "passive"))
      (node (ref "R_CV_FREQ_BIAS3") (pin "1") (pinfunction "1_1") (pintype "passive"))
      (node (ref "R_CV_FREQ_STAB3") (pin "1") (pinfunction "1_1") (pintype "passive"))
    )
    (net (code "45") (name "FREQ_CTRL_VCOB") (class "Default")
      (node (ref "3340B") (pin "15") (pinfunction "FREQ_CTRL_15") (pintype "bidirectional"))
      (node (ref "R_CV_FREQ1") (pin "1") (pinfunction "1_1") (pintype "passive"))
      (node (ref "R_CV_FREQ_BIAS1") (pin "1") (pinfunction "1_1") (pintype "passive"))
      (node (ref "R_CV_FREQ_STAB1") (pin "1") (pinfunction "1_1") (pintype "passive"))
    )
    (net (code "46") (name "FREQ_CV_VCF") (class "Default")
      (node (ref "R1_VCF") (pin "1") (pinfunction "1_1") (pintype "passive"))
      (node (ref "R2_VCF") (pin "1") (pinfunction "1_1") (pintype "passive"))
      (node (ref "VCF") (pin "12") (pinfunction "FREQ_CV_12") (pintype "bidirectional"))
    )
    (net (code "47") (name "GAIN1_A") (class "Default")
      (node (ref "MIXER_A") (pin "3") (pinfunction "GAIN_VCA_3") (pintype "bidirectional"))
      (node (ref "U1") (pin "17") (pinfunction "VOUT_7_17") (pintype "tri_state"))
    )
    (net (code "48") (name "GAIN1_B") (class "Default")
      (node (ref "MIXER_B") (pin "3") (pinfunction "GAIN_VCA_3") (pintype "bidirectional"))
      (node (ref "U1") (pin "24") (pinfunction "VOUT_11_24") (pintype "tri_state"))
    )
    (net (code "49") (name "GAIN2_A") (class "Default")
      (node (ref "MIXER_A") (pin "6") (pinfunction "GAIN_VCA_6") (pintype "bidirectional"))
      (node (ref "U1") (pin "21") (pinfunction "VOUT_8_21") (pintype "tri_state"))
    )
    (net (code "50") (name "GAIN2_B") (class "Default")
      (node (ref "MIXER_B") (pin "6") (pinfunction "GAIN_VCA_6") (pintype "bidirectional"))
      (node (ref "U1") (pin "25") (pinfunction "VOUT_12_25") (pintype "tri_state"))
    )
    (net (code "51") (name "GAIN3_A") (class "Default")
      (node (ref "MIXER_A") (pin "11") (pinfunction "GAIN_VCA_11") (pintype "bidirectional"))
      (node (ref "U1") (pin "16") (pinfunction "VOUT_6_16") (pintype "tri_state"))
    )
    (net (code "52") (name "GAIN3_B") (class "Default")
      (node (ref "MIXER_B") (pin "11") (pinfunction "GAIN_VCA_11") (pintype "bidirectional"))
      (node (ref "U1") (pin "22") (pinfunction "VOUT_9_22") (pintype "tri_state"))
    )
    (net (code "53") (name "GAIN4_A") (class "Default")
      (node (ref "MIXER_A") (pin "14") (pinfunction "GAIN_VCA_14") (pintype "bidirectional"))
      (node (ref "U1") (pin "15") (pinfunction "VOUT_5_15") (pintype "tri_state"))
    )
    (net (code "54") (name "GAIN4_B") (class "Default")
      (node (ref "MIXER_B") (pin "14") (pinfunction "GAIN_VCA_14") (pintype "bidirectional"))
      (node (ref "U1") (pin "23") (pinfunction "VOUT_10_23") (pintype "tri_state"))
    )
    (net (code "55") (name "HARD_SYNC_VCOA") (class "Default")
      (node (ref "3340A") (pin "6") (pinfunction "HARD_SYNC_6") (pintype "bidirectional"))
      (node (ref "C1_SYNC3") (pin "2") (pinfunction "2_2") (pintype "passive"))
    )
    (net (code "56") (name "HARD_SYNC_VCOB") (class "Default")
      (node (ref "3340B") (pin "6") (pinfunction "HARD_SYNC_6") (pintype "bidirectional"))
      (node (ref "C1_SYNC1") (pin "2") (pinfunction "2_2") (pintype "passive"))
    )
    (net (code "57") (name "IA_VCO13700") (class "Default")
      (node (ref "REE_2") (pin "1") (pinfunction "1_1") (pintype "passive"))
      (node (ref "VCO2") (pin "16") (pinfunction "I_BIAS_16") (pintype "input"))
    )
    (net (code "58") (name "IN1_MIXERA") (class "Default")
      (node (ref "CIN1_MIXERA") (pin "1") (pinfunction "1_1") (pintype "passive"))
      (node (ref "JP_TRIOUT_VCO3340B") (pin "2") (pinfunction "2_2") (pintype "passive"))
    )
    (net (code "59") (name "IN1_VCF") (class "Default")
      (node (ref "RC1_VCF") (pin "2") (pinfunction "2_2") (pintype "passive"))
      (node (ref "RF1_VCF") (pin "2") (pinfunction "2_2") (pintype "passive"))
      (node (ref "VCF") (pin "1") (pinfunction "IN_1") (pintype "bidirectional"))
    )
    (net (code "60") (name "IN2_MIXERA") (class "Default")
      (node (ref "CIN2_MIXERA") (pin "1") (pinfunction "1_1") (pintype "passive"))
      (node (ref "JP_OUT_VCO3340A") (pin "2") (pinfunction "2_2") (pintype "passive"))
      (node (ref "JP_OUT_VCO3340A2") (pin "1") (pinfunction "1_1") (pintype "passive"))
    )
    (net (code "61") (name "IN2_MIXERB") (class "Default")
      (node (ref "CIN2_MIXERB") (pin "1") (pinfunction "1_1") (pintype "passive"))
      (node (ref "JP8") (pin "2") (pinfunction "2_2") (pintype "passive"))
    )
    (net (code "62") (name "IN2_VCF") (class "Default")
      (node (ref "RB1_VCF") (pin "2") (pinfunction "2_2") (pintype "passive"))
      (node (ref "RC2_VCF") (pin "1") (pinfunction "1_1") (pintype "passive"))
      (node (ref "RF2_VCF") (pin "1") (pinfunction "1_1") (pintype "passive"))
      (node (ref "VCF") (pin "2") (pinfunction "IN_2") (pintype "bidirectional"))
    )
    (net (code "63") (name "IN3_MIXERA") (class "Default")
      (node (ref "CIN3_MIXERA") (pin "1") (pinfunction "1_1") (pintype "passive"))
      (node (ref "JP_SAWOUT_VCO3340B") (pin "2") (pinfunction "2_2") (pintype "passive"))
    )
    (net (code "64") (name "IN3_MIXERB") (class "Default")
      (node (ref "CIN3_MIXERB") (pin "1") (pinfunction "1_1") (pintype "passive"))
      (node (ref "JP9") (pin "2") (pinfunction "2_2") (pintype "passive"))
    )
    (net (code "65") (name "IN3_VCF") (class "Default")
      (node (ref "RB3_VCF") (pin "2") (pinfunction "2_2") (pintype "passive"))
      (node (ref "RC3") (pin "1") (pinfunction "1_1") (pintype "passive"))
      (node (ref "RF3") (pin "1") (pinfunction "1_1") (pintype "passive"))
      (node (ref "VCF") (pin "17") (pinfunction "IN_17") (pintype "bidirectional"))
    )
    (net (code "66") (name "IN4_MIXERA") (class "Default")
      (node (ref "CIN4_MIXERA") (pin "1") (pinfunction "1_1") (pintype "passive"))
      (node (ref "JP_PULSEOUT_VCO3340B") (pin "2") (pinfunction "2_2") (pintype "passive"))
    )
    (net (code "67") (name "IN4_MIXERB") (class "Default")
      (node (ref "CIN4_MIXERB") (pin "1") (pinfunction "1_1") (pintype "passive"))
      (node (ref "JP7") (pin "2") (pinfunction "2_2") (pintype "passive"))
    )
    (net (code "68") (name "IN4_VCF") (class "Default")
      (node (ref "RB2") (pin "2") (pinfunction "2_2") (pintype "passive"))
      (node (ref "RC4") (pin "1") (pinfunction "1_1") (pintype "passive"))
      (node (ref "RF4") (pin "1") (pinfunction "1_1") (pintype "passive"))
      (node (ref "VCF") (pin "18") (pinfunction "IN_18") (pintype "bidirectional"))
    )
    (net (code "69") (name "INPUT_CURRENT_SUM_STG") (class "Default")
      (node (ref "JP1") (pin "1") (pinfunction "1_1") (pintype "passive"))
      (node (ref "JP1") (pin "2") (pinfunction "2_2") (pintype "passive"))
      (node (ref "OPAMP_SUM_STG") (pin "2") (pinfunction "-IN_2") (pintype "input"))
      (node (ref "SUM_STG_C") (pin "2") (pinfunction "2_2") (pintype "passive"))
      (node (ref "SUM_STG_HEADER") (pin "1") (pinfunction "1_1") (pintype "passive"))
      (node (ref "SUM_STG_HEADER") (pin "2") (pinfunction "2_2") (pintype "passive"))
      (node (ref "SUM_STG_HEADER") (pin "3") (pinfunction "3_3") (pintype "passive"))
      (node (ref "SUM_STG_HEADER") (pin "4") (pinfunction "4_4") (pintype "passive"))
      (node (ref "SUM_STG_HEADER") (pin "5") (pinfunction "5_5") (pintype "passive"))
      (node (ref "SUM_STG_HEADER") (pin "6") (pinfunction "6_6") (pintype "passive"))
      (node (ref "SUM_STG_HEADER") (pin "7") (pinfunction "7_7") (pintype "passive"))
      (node (ref "SUM_STG_HEADER") (pin "8") (pinfunction "8_8") (pintype "passive"))
      (node (ref "SUM_STG_R") (pin "2") (pinfunction "2_2") (pintype "passive"))
      (node (ref "VCA") (pin "5") (pinfunction "OUT_5") (pintype "output"))
    )
    (net (code "70") (name "INPUT_FM_3340") (class "Default")
      (node (ref "JP_OUT_VCO3340A1") (pin "2") (pinfunction "2_2") (pintype "passive"))
      (node (ref "RTEST_13700FREQ2") (pin "1") (pinfunction "1_1") (pintype "passive"))
    )
    (net (code "71") (name "IN_VCA") (class "Default")
      (node (ref "R1_VCA") (pin "1") (pinfunction "1_1") (pintype "passive"))
      (node (ref "VCF_JUMPER") (pin "2") (pinfunction "2_2") (pintype "passive"))
    )
    (net (code "72") (name "IN_VCF") (class "Default")
      (node (ref "C_IN2") (pin "2") (pinfunction "2_2") (pintype "passive"))
      (node (ref "VCF_JUMPER") (pin "4") (pinfunction "4_4") (pintype "passive"))
    )
    (net (code "73") (name "IN_VCFORDER") (class "Default")
      (node (ref "R_PD_4TH_ORDER_VCF") (pin "2") (pinfunction "2_2") (pintype "passive"))
      (node (ref "STM32L432KC_CONN_") (pin "3.14") (pinfunction "PB5_3.14") (pintype "bidirectional"))
      (node (ref "VCF_ANALOG_SW") (pin "1") (pinfunction "IN_1") (pintype "input"))
      (node (ref "VCF_ANALOG_SW") (pin "16") (pinfunction "IN_16") (pintype "input"))
    )
    (net (code "74") (name "JACK_SUM_STG") (class "Default")
      (node (ref "COUT_SUM_STG") (pin "-") (pinfunction "-_-") (pintype "passive"))
      (node (ref "OUT") (pin "1") (pinfunction "1_1") (pintype "passive"))
    )
    (net (code "75") (name "LD2_RED") (class "Default")
      (node (ref "R_LD2") (pin "1") (pinfunction "1_1") (pintype "passive"))
      (node (ref "STM32L432KC_CONN_") (pin "3.13") (pinfunction "PA11_3.13") (pintype "bidirectional"))
    )
    (net (code "76") (name "LD3_GREEN") (class "Default")
      (node (ref "STM32L432KC_CONN_") (pin "4.15") (pinfunction "PB3_4.15") (pintype "bidirectional"))
    )
    (net (code "77") (name "LINEAR_CTRL_VCOA") (class "Default")
      (node (ref "3340A") (pin "13") (pinfunction "LINEAR_CTRL_13") (pintype "bidirectional"))
      (node (ref "R10_3") (pin "1") (pinfunction "1_1") (pintype "passive"))
      (node (ref "R8_3") (pin "1") (pinfunction "1_1") (pintype "passive"))
    )
    (net (code "78") (name "LINEAR_CTRL_VCOB") (class "Default")
      (node (ref "3340B") (pin "13") (pinfunction "LINEAR_CTRL_13") (pintype "bidirectional"))
      (node (ref "R10_1") (pin "1") (pinfunction "1_1") (pintype "passive"))
      (node (ref "R8_1") (pin "1") (pinfunction "1_1") (pintype "passive"))
    )
    (net (code "79") (name "N$4") (class "Default")
      (node (ref "JP_MIXER_A") (pin "4") (pinfunction "4_4") (pintype "passive"))
      (node (ref "MIXER_A") (pin "4") (pinfunction "I_OUT_4") (pintype "bidirectional"))
    )
    (net (code "80") (name "Net-(3A-D)") (class "Default")
      (node (ref "3") (pin "2") (pinfunction "D_2") (pintype "passive"))
      (node (ref "C1_1") (pin "2") (pinfunction "2_2") (pintype "passive"))
      (node (ref "R1_7") (pin "2") (pinfunction "2_2") (pintype "passive"))
    )
    (net (code "81") (name "Net-(3C-D)") (class "Default")
      (node (ref "3") (pin "10") (pinfunction "D_10") (pintype "passive"))
      (node (ref "C3_1") (pin "2") (pinfunction "2_2") (pintype "passive"))
      (node (ref "R3_4") (pin "2") (pinfunction "2_2") (pintype "passive"))
    )
    (net (code "82") (name "Net-(3D-D)") (class "Default")
      (node (ref "3") (pin "7") (pinfunction "D_7") (pintype "passive"))
      (node (ref "C2_1") (pin "2") (pinfunction "2_2") (pintype "passive"))
      (node (ref "R2_7") (pin "2") (pinfunction "2_2") (pintype "passive"))
    )
    (net (code "83") (name "Net-(3D-S)") (class "Default")
      (node (ref "3") (pin "6") (pinfunction "S_6") (pintype "passive"))
      (node (ref "R2S_1") (pin "2") (pinfunction "2_2") (pintype "passive"))
    )
    (net (code "84") (name "Net-(C1_SYNC1-Pad1)") (class "Default")
      (node (ref "C1_SYNC1") (pin "1") (pinfunction "1_1") (pintype "passive"))
      (node (ref "R_SYNC1") (pin "2") (pinfunction "2_2") (pintype "passive"))
    )
    (net (code "85") (name "Net-(C2_VCA-Pad2)") (class "Default")
      (node (ref "C2_VCA") (pin "2") (pinfunction "2_2") (pintype "passive"))
      (node (ref "R1_VCA") (pin "2") (pinfunction "2_2") (pintype "passive"))
      (node (ref "R2_VCA") (pin "2") (pinfunction "2_2") (pintype "passive"))
    )
    (net (code "86") (name "Net-(C4_1-Pad1)") (class "Default")
      (node (ref "C4_1") (pin "1") (pinfunction "1_1") (pintype "passive"))
      (node (ref "R10_1") (pin "2") (pinfunction "2_2") (pintype "passive"))
    )
    (net (code "87") (name "Net-(C4_3-Pad1)") (class "Default")
      (node (ref "C4_3") (pin "1") (pinfunction "1_1") (pintype "passive"))
      (node (ref "R10_3") (pin "2") (pinfunction "2_2") (pintype "passive"))
    )
    (net (code "88") (name "Net-(CIN1_MIXERA-Pad2)") (class "Default")
      (node (ref "CIN1_MIXERA") (pin "2") (pinfunction "2_2") (pintype "passive"))
      (node (ref "RIN1_MIXERA") (pin "2") (pinfunction "2_2") (pintype "passive"))
    )
    (net (code "89") (name "Net-(CIN2_MIXERA-Pad2)") (class "Default")
      (node (ref "CIN2_MIXERA") (pin "2") (pinfunction "2_2") (pintype "passive"))
      (node (ref "RIN2_MIXERA") (pin "2") (pinfunction "2_2") (pintype "passive"))
    )
    (net (code "90") (name "Net-(CIN2_MIXERB-Pad2)") (class "Default")
      (node (ref "CIN2_MIXERB") (pin "2") (pinfunction "2_2") (pintype "passive"))
      (node (ref "RIN2_MIXERB") (pin "2") (pinfunction "2_2") (pintype "passive"))
    )
    (net (code "91") (name "Net-(CIN3_MIXERA-Pad2)") (class "Default")
      (node (ref "CIN3_MIXERA") (pin "2") (pinfunction "2_2") (pintype "passive"))
      (node (ref "RIN3_MIXERA") (pin "2") (pinfunction "2_2") (pintype "passive"))
    )
    (net (code "92") (name "Net-(CIN3_MIXERB-Pad2)") (class "Default")
      (node (ref "CIN3_MIXERB") (pin "2") (pinfunction "2_2") (pintype "passive"))
      (node (ref "RIN3_MIXERB") (pin "2") (pinfunction "2_2") (pintype "passive"))
    )
    (net (code "93") (name "Net-(CIN4_MIXERA-Pad2)") (class "Default")
      (node (ref "CIN4_MIXERA") (pin "2") (pinfunction "2_2") (pintype "passive"))
      (node (ref "RIN4_MIXERA") (pin "2") (pinfunction "2_2") (pintype "passive"))
    )
    (net (code "94") (name "Net-(CIN4_MIXERB-Pad2)") (class "Default")
      (node (ref "CIN4_MIXERB") (pin "2") (pinfunction "2_2") (pintype "passive"))
      (node (ref "RIN4_MIXERB") (pin "2") (pinfunction "2_2") (pintype "passive"))
    )
    (net (code "95") (name "Net-(CIN4_MIXERB1-Pad1)") (class "Default")
      (node (ref "CIN4_MIXERB1") (pin "1") (pinfunction "1_1") (pintype "passive"))
      (node (ref "JP_OUT_VCO3340A2") (pin "2") (pinfunction "2_2") (pintype "passive"))
    )
    (net (code "96") (name "Net-(CIN4_MIXERB1-Pad2)") (class "Default")
      (node (ref "CIN4_MIXERB1") (pin "2") (pinfunction "2_2") (pintype "passive"))
      (node (ref "RIN4_MIXERB1") (pin "2") (pinfunction "2_2") (pintype "passive"))
    )
    (net (code "97") (name "Net-(CONVLOG2-C1)") (class "Default")
      (node (ref "CONVLOG2") (pin "6") (pinfunction "C1_6") (pintype "passive"))
      (node (ref "EXPCONV2") (pin "2") (pinfunction "-IN_2") (pintype "input"))
      (node (ref "RBIAS_EXPCONV2") (pin "2") (pinfunction "2_2") (pintype "passive"))
    )
    (net (code "98") (name "Net-(CONVLOG2-E1)") (class "Default")
      (node (ref "CONVLOG2") (pin "1") (pinfunction "E1_1") (pintype "passive"))
      (node (ref "CONVLOG2") (pin "4") (pinfunction "E2_4") (pintype "passive"))
      (node (ref "R5_EXPCONV2") (pin "1") (pinfunction "1_1") (pintype "passive"))
    )
    (net (code "99") (name "Net-(CONV_ITOV_OUT--IN)") (class "Default")
      (node (ref "CONV_ITOV_OUT") (pin "2") (pinfunction "-IN_2") (pintype "input"))
      (node (ref "C_CONV_ITOV_OUT") (pin "1") (pinfunction "1_1") (pintype "passive"))
      (node (ref "JP_MIXER_A") (pin "1") (pinfunction "1_1") (pintype "passive"))
      (node (ref "JP_MIXER_A") (pin "3") (pinfunction "3_3") (pintype "passive"))
      (node (ref "JP_MIXER_A") (pin "5") (pinfunction "5_5") (pintype "passive"))
      (node (ref "JP_MIXER_A") (pin "7") (pinfunction "7_7") (pintype "passive"))
      (node (ref "JP_MIXER_B") (pin "1") (pinfunction "1_1") (pintype "passive"))
      (node (ref "JP_MIXER_B") (pin "3") (pinfunction "3_3") (pintype "passive"))
      (node (ref "JP_MIXER_B") (pin "5") (pinfunction "5_5") (pintype "passive"))
      (node (ref "JP_MIXER_B") (pin "7") (pinfunction "7_7") (pintype "passive"))
      (node (ref "R_CONV_ITOV_OUT") (pin "1") (pinfunction "1_1") (pintype "passive"))
    )
    (net (code "100") (name "Net-(CSTAB1_MIXERA-Pad2)") (class "Default")
      (node (ref "CSTAB1_MIXERA") (pin "2") (pinfunction "2_2") (pintype "passive"))
      (node (ref "RSTAB1_MIXERA") (pin "2") (pinfunction "2_2") (pintype "passive"))
    )
    (net (code "101") (name "Net-(CSTAB2-Pad1)") (class "Default")
      (node (ref "CSTAB2") (pin "1") (pinfunction "1_1") (pintype "passive"))
      (node (ref "JP_OUT_VCO3340A1") (pin "1") (pinfunction "1_1") (pintype "passive"))
    )
    (net (code "102") (name "Net-(CSTAB2_MIXERA-Pad2)") (class "Default")
      (node (ref "CSTAB2_MIXERA") (pin "2") (pinfunction "2_2") (pintype "passive"))
      (node (ref "RSTAB2_MIXERA") (pin "2") (pinfunction "2_2") (pintype "passive"))
    )
    (net (code "103") (name "Net-(CSTAB2_MIXERB-Pad2)") (class "Default")
      (node (ref "CSTAB2_MIXERB") (pin "2") (pinfunction "2_2") (pintype "passive"))
      (node (ref "RSTAB2_MIXERB") (pin "2") (pinfunction "2_2") (pintype "passive"))
    )
    (net (code "104") (name "Net-(CSTAB3-Pad2)") (class "Default")
      (node (ref "CSTAB3") (pin "2") (pinfunction "2_2") (pintype "passive"))
      (node (ref "RSTAB4_MIXERB2") (pin "2") (pinfunction "2_2") (pintype "passive"))
    )
    (net (code "105") (name "Net-(CSTAB3_MIXERA-Pad2)") (class "Default")
      (node (ref "CSTAB3_MIXERA") (pin "2") (pinfunction "2_2") (pintype "passive"))
      (node (ref "RSTAB3_MIXERA") (pin "2") (pinfunction "2_2") (pintype "passive"))
    )
    (net (code "106") (name "Net-(CSTAB3_MIXERB-Pad2)") (class "Default")
      (node (ref "CSTAB3_MIXERB") (pin "2") (pinfunction "2_2") (pintype "passive"))
      (node (ref "RSTAB3_MIXERB") (pin "2") (pinfunction "2_2") (pintype "passive"))
    )
    (net (code "107") (name "Net-(CSTAB4_MIXERA-Pad2)") (class "Default")
      (node (ref "CSTAB4_MIXERA") (pin "2") (pinfunction "2_2") (pintype "passive"))
      (node (ref "RSTAB4_MIXERA") (pin "2") (pinfunction "2_2") (pintype "passive"))
    )
    (net (code "108") (name "Net-(CSTAB8-Pad2)") (class "Default")
      (node (ref "CSTAB8") (pin "2") (pinfunction "2_2") (pintype "passive"))
      (node (ref "RSTAB4_MIXERB") (pin "2") (pinfunction "2_2") (pintype "passive"))
    )
    (net (code "109") (name "Net-(C_CV_FREQ_STAB1-Pad2)") (class "Default")
      (node (ref "C_CV_FREQ_STAB1") (pin "2") (pinfunction "2_2") (pintype "passive"))
      (node (ref "R_CV_FREQ_STAB1") (pin "2") (pinfunction "2_2") (pintype "passive"))
    )
    (net (code "110") (name "Net-(C_CV_FREQ_STAB3-Pad2)") (class "Default")
      (node (ref "C_CV_FREQ_STAB3") (pin "2") (pinfunction "2_2") (pintype "passive"))
      (node (ref "R_CV_FREQ_STAB3") (pin "2") (pinfunction "2_2") (pintype "passive"))
    )
    (net (code "111") (name "Net-(C_IN2-Pad1)") (class "Default")
      (node (ref "C_IN2") (pin "1") (pinfunction "1_1") (pintype "passive"))
      (node (ref "RC1_VCF") (pin "1") (pinfunction "1_1") (pintype "passive"))
    )
    (net (code "112") (name "Net-(D_2-PadC)") (class "Default")
      (node (ref "D_2") (pin "C") (pinfunction "C_C") (pintype "passive"))
      (node (ref "R_LIM_2") (pin "2") (pinfunction "2_2") (pintype "passive"))
    )
    (net (code "113") (name "Net-(EXPCONV2-OUT)") (class "Default")
      (node (ref "EXPCONV2") (pin "6") (pinfunction "OUT_6") (pintype "output"))
      (node (ref "R5_EXPCONV2") (pin "2") (pinfunction "2_2") (pintype "passive"))
    )
    (net (code "114") (name "Net-(HEADER_EXPCONV2-Pad1)") (class "Default")
      (node (ref "HEADER_EXPCONV2") (pin "1") (pinfunction "1_1") (pintype "passive"))
      (node (ref "RTEST_LOG2") (pin "1") (pinfunction "1_1") (pintype "passive"))
    )
    (net (code "115") (name "Net-(LD2_RED-PadA)") (class "Default")
      (node (ref "LD2_RED") (pin "A") (pinfunction "A_A") (pintype "passive"))
      (node (ref "R_LD2") (pin "2") (pinfunction "2_2") (pintype "passive"))
    )
    (net (code "116") (name "Net-(MIXER_BB-I_IN)") (class "Default")
      (node (ref "MIXER_B") (pin "2") (pinfunction "I_IN_2") (pintype "bidirectional"))
      (node (ref "RIN4_MIXERB1") (pin "1") (pinfunction "1_1") (pintype "passive"))
      (node (ref "RSTAB4_MIXERB2") (pin "1") (pinfunction "1_1") (pintype "passive"))
    )
    (net (code "117") (name "Net-(MIXER_BB-I_OUT)") (class "Default")
      (node (ref "CSTAB2") (pin "2") (pinfunction "2_2") (pintype "passive"))
      (node (ref "MIXER_B") (pin "4") (pinfunction "I_OUT_4") (pintype "bidirectional"))
      (node (ref "RSTAB4_MIXERB1") (pin "2") (pinfunction "2_2") (pintype "passive"))
    )
    (net (code "118") (name "Net-(MIXER_BE-I_OUT)") (class "Default")
      (node (ref "JP_MIXER_B") (pin "8") (pinfunction "8_8") (pintype "passive"))
      (node (ref "MIXER_B") (pin "12") (pinfunction "I_OUT_12") (pintype "bidirectional"))
    )
    (net (code "119") (name "Net-(SUBBASS2-1J)") (class "Default")
      (node (ref "SUBBASS2") (pin "10") (pinfunction "1J_10") (pintype "input"))
      (node (ref "SUBBASS2") (pin "14") (pinfunction "1~{Q}_14") (pintype "output"))
    )
    (net (code "120") (name "Net-(VCAC-IN_N)") (class "Default")
      (node (ref "R5_VCA") (pin "2") (pinfunction "2_2") (pintype "passive"))
      (node (ref "VCA") (pin "4") (pinfunction "IN_N_4") (pintype "input"))
    )
    (net (code "121") (name "Net-(VCAC-I_BIAS)") (class "Default")
      (node (ref "R_GAIN_VCA") (pin "2") (pinfunction "2_2") (pintype "passive"))
      (node (ref "VCA") (pin "1") (pinfunction "I_BIAS_1") (pintype "input"))
    )
    (net (code "122") (name "Net-(VCF_ANALOG_SWA-S)") (class "Default")
      (node (ref "CRES_VCF") (pin "1") (pinfunction "1_1") (pintype "passive"))
      (node (ref "VCF_ANALOG_SW") (pin "14") (pinfunction "S_14") (pintype "bidirectional"))
      (node (ref "VCF_ANALOG_SW") (pin "3") (pinfunction "S_3") (pintype "bidirectional"))
    )
    (net (code "123") (name "Net-(VCO2A-B)") (class "Default")
      (node (ref "CF_2") (pin "2") (pinfunction "2_2") (pintype "passive"))
      (node (ref "VCO2") (pin "5") (pinfunction "OUT_5") (pintype "output"))
      (node (ref "VCO2") (pin "7") (pinfunction "B_7") (pintype "passive"))
    )
    (net (code "124") (name "Net-(VCO2B-B)") (class "Default")
      (node (ref "RA_2") (pin "2") (pinfunction "2_2") (pintype "passive"))
      (node (ref "VCO2") (pin "10") (pinfunction "B_10") (pintype "passive"))
      (node (ref "VCO2") (pin "12") (pinfunction "OUT_12") (pintype "output"))
      (node (ref "VCO2") (pin "14") (pinfunction "IN_P_14") (pintype "input"))
      (node (ref "VCO2") (pin "3") (pinfunction "IN_P_3") (pintype "input"))
    )
    (net (code "125") (name "OUT1_VCF") (class "Default")
      (node (ref "RC2_VCF") (pin "2") (pinfunction "2_2") (pintype "passive"))
      (node (ref "RF1_VCF") (pin "1") (pinfunction "1_1") (pintype "passive"))
      (node (ref "VCF") (pin "7") (pinfunction "OUT_7") (pintype "bidirectional"))
    )
    (net (code "126") (name "OUT2_VCF") (class "Default")
      (node (ref "RC3") (pin "2") (pinfunction "2_2") (pintype "passive"))
      (node (ref "RF2_VCF") (pin "2") (pinfunction "2_2") (pintype "passive"))
      (node (ref "VCF") (pin "6") (pinfunction "OUT_6") (pintype "bidirectional"))
      (node (ref "VCF_ANALOG_SW") (pin "15") (pinfunction "D_15") (pintype "bidirectional"))
    )
    (net (code "127") (name "OUT3_VCF") (class "Default")
      (node (ref "RC4") (pin "2") (pinfunction "2_2") (pintype "passive"))
      (node (ref "RF3") (pin "2") (pinfunction "2_2") (pintype "passive"))
      (node (ref "VCF") (pin "15") (pinfunction "OUT_15") (pintype "bidirectional"))
    )
    (net (code "128") (name "OUT4_VCF") (class "Default")
      (node (ref "RF4") (pin "2") (pinfunction "2_2") (pintype "passive"))
      (node (ref "VCF") (pin "10") (pinfunction "OUT_10") (pintype "bidirectional"))
      (node (ref "VCF_ANALOG_SW") (pin "2") (pinfunction "D_2") (pintype "bidirectional"))
    )
    (net (code "129") (name "OUT_EXPCONV_VCO13700") (class "Default")
      (node (ref "CONVLOG2") (pin "3") (pinfunction "C2_3") (pintype "passive"))
      (node (ref "HEADER_EXPCONV2") (pin "2") (pinfunction "2_2") (pintype "passive"))
    )
    (net (code "130") (name "OUT_MIXER") (class "Default")
      (node (ref "CONV_ITOV_OUT") (pin "6") (pinfunction "OUT_6") (pintype "output"))
      (node (ref "C_CONV_ITOV_OUT") (pin "2") (pinfunction "2_2") (pintype "passive"))
      (node (ref "R_CONV_ITOV_OUT") (pin "2") (pinfunction "2_2") (pintype "passive"))
      (node (ref "VCF_JUMPER") (pin "3") (pinfunction "3_3") (pintype "passive"))
    )
    (net (code "131") (name "OUT_SUM_STG") (class "Default")
      (node (ref "OPAMP_SUM_STG") (pin "6") (pinfunction "OUT_6") (pintype "output"))
      (node (ref "ROUT_SUM_STG") (pin "2") (pinfunction "2_2") (pintype "passive"))
      (node (ref "SUM_STG_C") (pin "1") (pinfunction "1_1") (pintype "passive"))
      (node (ref "SUM_STG_R") (pin "1") (pinfunction "1_1") (pintype "passive"))
    )
    (net (code "132") (name "OUT_VCF") (class "Default")
      (node (ref "CRES_VCF") (pin "2") (pinfunction "2_2") (pintype "passive"))
      (node (ref "RRI_VCF") (pin "2") (pinfunction "2_2") (pintype "passive"))
      (node (ref "VCF_JUMPER") (pin "1") (pinfunction "1_1") (pintype "passive"))
    )
    (net (code "133") (name "PNP1_B_VCO13700") (class "Default")
      (node (ref "CONVLOG2") (pin "2") (pinfunction "B1_2") (pintype "passive"))
      (node (ref "R1_EXPCONV2") (pin "1") (pinfunction "1_1") (pintype "passive"))
      (node (ref "R2_EXPCONV2") (pin "1") (pinfunction "1_1") (pintype "passive"))
    )
    (net (code "134") (name "PNP2_B_VCO13700") (class "Default")
      (node (ref "CONVLOG2") (pin "5") (pinfunction "B2_5") (pintype "passive"))
      (node (ref "R3_EXPCONV2") (pin "1") (pinfunction "1_1") (pintype "passive"))
      (node (ref "R4_EXPCONV2") (pin "1") (pinfunction "1_1") (pintype "passive"))
    )
    (net (code "135") (name "POT2_SUM_STG") (class "Default")
      (node (ref "COUT_SUM_STG") (pin "+") (pinfunction "+_+") (pintype "passive"))
      (node (ref "POT_SUM_STG") (pin "2") (pinfunction "S_2") (pintype "passive"))
    )
    (net (code "136") (name "POT3_SUM_STG") (class "Default")
      (node (ref "POT_SUM_STG") (pin "3") (pinfunction "E_3") (pintype "passive"))
      (node (ref "ROUT_SUM_STG") (pin "1") (pinfunction "1_1") (pintype "passive"))
    )
    (net (code "137") (name "PULSE_OUT_VCOA") (class "Default")
      (node (ref "3") (pin "11") (pinfunction "S_11") (pintype "passive"))
      (node (ref "R3S_1") (pin "2") (pinfunction "2_2") (pintype "passive"))
    )
    (net (code "138") (name "PULSE_VCOA") (class "Default")
      (node (ref "3340A") (pin "4") (pinfunction "PULSE_OUT_4") (pintype "bidirectional"))
      (node (ref "C3_1") (pin "1") (pinfunction "1_1") (pintype "passive"))
      (node (ref "R6_3") (pin "2") (pinfunction "2_2") (pintype "passive"))
      (node (ref "TP_PULSE3") (pin "P$1") (pinfunction "P$1_P$1") (pintype "passive"))
    )
    (net (code "139") (name "REFOUT") (class "Default")
      (node (ref "CDEC_VREF") (pin "1") (pinfunction "1_1") (pintype "passive"))
      (node (ref "U1") (pin "5") (pinfunction "REFOUT/REFIN_5") (pintype "bidirectional"))
    )
    (net (code "140") (name "RES_CUR_IN_VCF") (class "Default")
      (node (ref "RRI_VCF") (pin "1") (pinfunction "1_1") (pintype "passive"))
      (node (ref "VCF") (pin "8") (pinfunction "IN_RES_8") (pintype "bidirectional"))
    )
    (net (code "141") (name "RES_CUR_VCF") (class "Default")
      (node (ref "R_RES_VCF") (pin "1") (pinfunction "1_1") (pintype "passive"))
      (node (ref "VCF") (pin "9") (pinfunction "RES_CUR_9") (pintype "bidirectional"))
    )
    (net (code "142") (name "RST") (class "Default")
      (node (ref "STM32L432KC_CONN_") (pin "4.7") (pinfunction "PA6_4.7") (pintype "bidirectional"))
      (node (ref "U1") (pin "37") (pinfunction "~{RESET}_37") (pintype "input"))
    )
    (net (code "143") (name "SAW_3340_VCOA") (class "Default")
      (node (ref "C2_1") (pin "1") (pinfunction "1_1") (pintype "passive"))
      (node (ref "R7_3") (pin "1") (pinfunction "1_1") (pintype "passive"))
      (node (ref "TP_SAW3") (pin "P$1") (pinfunction "P$1_P$1") (pintype "passive"))
    )
    (net (code "144") (name "SAW_VCOA") (class "Default")
      (node (ref "3340A") (pin "8") (pinfunction "SAW_OUT_8") (pintype "bidirectional"))
      (node (ref "R7_3") (pin "2") (pinfunction "2_2") (pintype "passive"))
    )
    (net (code "145") (name "SAW_VCOB") (class "Default")
      (node (ref "3340B") (pin "8") (pinfunction "SAW_OUT_8") (pintype "bidirectional"))
      (node (ref "R7_1") (pin "2") (pinfunction "2_2") (pintype "passive"))
    )
    (net (code "146") (name "SCALE_VCOA") (class "Default")
      (node (ref "3340A") (pin "14") (pinfunction "SCALE_14") (pintype "bidirectional"))
      (node (ref "R11_3") (pin "1") (pinfunction "1_1") (pintype "passive"))
    )
    (net (code "147") (name "SCALE_VCOB") (class "Default")
      (node (ref "3340B") (pin "14") (pinfunction "SCALE_14") (pintype "bidirectional"))
      (node (ref "R11_1") (pin "1") (pinfunction "1_1") (pintype "passive"))
    )
    (net (code "148") (name "SCL") (class "Default")
      (node (ref "IC_EEPROM") (pin "6") (pinfunction "SCL_6") (pintype "input"))
      (node (ref "R_PU_SCL") (pin "1") (pinfunction "1_1") (pintype "passive"))
      (node (ref "STM32L432KC_CONN_") (pin "4.6") (pinfunction "PA7_4.6") (pintype "bidirectional"))
    )
    (net (code "149") (name "SDA") (class "Default")
      (node (ref "IC_EEPROM") (pin "5") (pinfunction "SDA_5") (pintype "bidirectional"))
      (node (ref "R_PU_DSA") (pin "1") (pinfunction "1_1") (pintype "passive"))
      (node (ref "STM32L432KC_CONN_") (pin "3.15") (pinfunction "PB4_3.15") (pintype "bidirectional"))
    )
    (net (code "150") (name "SOFT_SYNC_VCOA") (class "Default")
      (node (ref "3340A") (pin "9") (pinfunction "SOFT_SYNC_9") (pintype "bidirectional"))
      (node (ref "C2_SYNC3") (pin "2") (pinfunction "2_2") (pintype "passive"))
    )
    (net (code "151") (name "SOFT_SYNC_VCOB") (class "Default")
      (node (ref "3340B") (pin "9") (pinfunction "SOFT_SYNC_9") (pintype "bidirectional"))
      (node (ref "C2_SYNC1") (pin "2") (pinfunction "2_2") (pintype "passive"))
    )
    (net (code "152") (name "SPI_CLK") (class "Default")
      (node (ref "STM32L432KC_CONN_") (pin "4.11") (pinfunction "PA1_4.11") (pintype "bidirectional"))
      (node (ref "U1") (pin "49") (pinfunction "SCLK/SCL_49") (pintype "input"))
    )
    (net (code "153") (name "SPI_MOSI") (class "Default")
      (node (ref "STM32L432KC_CONN_") (pin "3.5") (pinfunction "PA12_3.5") (pintype "bidirectional"))
      (node (ref "U1") (pin "50") (pinfunction "DIN/SDA_50") (pintype "bidirectional"))
    )
    (net (code "154") (name "SUBBASS_IN_VCO13700") (class "Default")
      (node (ref "R_LIM_2") (pin "1") (pinfunction "1_1") (pintype "passive"))
      (node (ref "SUBBASS2") (pin "13") (pinfunction "1CP_13") (pintype "input"))
    )
    (net (code "155") (name "SW1") (class "Default")
      (node (ref "C_SW1") (pin "1") (pinfunction "1_1") (pintype "passive"))
      (node (ref "S1") (pin "3") (pinfunction "P_3") (pintype "passive"))
      (node (ref "S1") (pin "4") (pinfunction "P1_4") (pintype "passive"))
      (node (ref "STM32L432KC_CONN_") (pin "4.9") (pinfunction "PA4_4.9") (pintype "bidirectional"))
    )
    (net (code "156") (name "SYNC_3340_VCOA") (class "Default")
      (node (ref "3") (pin "15") (pinfunction "D_15") (pintype "passive"))
      (node (ref "C1_SYNC3") (pin "1") (pinfunction "1_1") (pintype "passive"))
      (node (ref "R_SYNC3") (pin "2") (pinfunction "2_2") (pintype "passive"))
    )
    (net (code "157") (name "SYNC_IN_VCOA") (class "Default")
      (node (ref "3") (pin "14") (pinfunction "S_14") (pintype "passive"))
      (node (ref "JP_SYNC_3340B_TO_A") (pin "1") (pinfunction "1_1") (pintype "passive"))
    )
    (net (code "158") (name "TEMPCO1_VCOA") (class "Default")
      (node (ref "3340A") (pin "1") (pinfunction "MUL_GAIN1_1") (pintype "bidirectional"))
      (node (ref "R1_4") (pin "1") (pinfunction "1_1") (pintype "passive"))
    )
    (net (code "159") (name "TEMPCO1_VCOB") (class "Default")
      (node (ref "3340B") (pin "1") (pinfunction "MUL_GAIN1_1") (pintype "bidirectional"))
      (node (ref "R1_3") (pin "1") (pinfunction "1_1") (pintype "passive"))
    )
    (net (code "160") (name "TEMPCO2_VCOA") (class "Default")
      (node (ref "3340A") (pin "2") (pinfunction "MUL_GAIN2_2") (pintype "bidirectional"))
      (node (ref "R2_4") (pin "1") (pinfunction "1_1") (pintype "passive"))
    )
    (net (code "161") (name "TEMPCO2_VCOB") (class "Default")
      (node (ref "3340B") (pin "2") (pinfunction "MUL_GAIN2_2") (pintype "bidirectional"))
      (node (ref "R2_3") (pin "1") (pinfunction "1_1") (pintype "passive"))
    )
    (net (code "162") (name "TIMING_CAP_VCOA") (class "Default")
      (node (ref "3340A") (pin "11") (pinfunction "TIMING_CAP_11") (pintype "bidirectional"))
      (node (ref "C_3") (pin "2") (pinfunction "2_2") (pintype "passive"))
    )
    (net (code "163") (name "TIMING_CAP_VCOB") (class "Default")
      (node (ref "3340B") (pin "11") (pinfunction "TIMING_CAP_11") (pintype "bidirectional"))
      (node (ref "C_1") (pin "2") (pinfunction "2_2") (pintype "passive"))
    )
    (net (code "164") (name "TRI_3340_VCOA") (class "Default")
      (node (ref "3340A") (pin "10") (pinfunction "TRI_OUT_10") (pintype "bidirectional"))
      (node (ref "C1_1") (pin "1") (pinfunction "1_1") (pintype "passive"))
      (node (ref "TP_TRI3") (pin "P$1") (pinfunction "P$1_P$1") (pintype "passive"))
    )
    (net (code "165") (name "TRI_OUT_VCOA") (class "Default")
      (node (ref "3") (pin "3") (pinfunction "S_3") (pintype "passive"))
      (node (ref "R1S_1") (pin "1") (pinfunction "1_1") (pintype "passive"))
    )
    (net (code "166") (name "USART_RX_RPI_TX") (class "Default")
      (node (ref "CONN_UART_RPI") (pin "2") (pinfunction "2_2") (pintype "passive"))
      (node (ref "STM32L432KC_CONN_") (pin "3.7") (pinfunction "PB7_3.7") (pintype "bidirectional"))
    )
    (net (code "167") (name "USART_TX_RPI_RX") (class "Default")
      (node (ref "CONN_UART_RPI") (pin "3") (pinfunction "3_3") (pintype "passive"))
      (node (ref "STM32L432KC_CONN_") (pin "3.8") (pinfunction "PB6_3.8") (pintype "bidirectional"))
    )
    (net (code "168") (name "VCO440A_OUT") (class "Default")
      (node (ref "JP_OUT_VCO3340A") (pin "1") (pinfunction "1_1") (pintype "passive"))
      (node (ref "R1S_1") (pin "2") (pinfunction "2_2") (pintype "passive"))
      (node (ref "R2S_1") (pin "1") (pinfunction "1_1") (pintype "passive"))
      (node (ref "R3S_1") (pin "1") (pinfunction "1_1") (pintype "passive"))
    )
    (net (code "169") (name "VCO3340B_PULSE_OUT") (class "Default")
      (node (ref "3340B") (pin "4") (pinfunction "PULSE_OUT_4") (pintype "bidirectional"))
      (node (ref "JP_PULSEOUT_VCO3340B") (pin "1") (pinfunction "1_1") (pintype "passive"))
      (node (ref "R6_1") (pin "2") (pinfunction "2_2") (pintype "passive"))
      (node (ref "TP_PULSE1") (pin "P$1") (pinfunction "P$1_P$1") (pintype "passive"))
    )
    (net (code "170") (name "VCO3340B_SAW_OUT") (class "Default")
      (node (ref "JP_SAWOUT_VCO3340B") (pin "1") (pinfunction "1_1") (pintype "passive"))
      (node (ref "JP_SYNC_3340B_TO_A") (pin "2") (pinfunction "2_2") (pintype "passive"))
      (node (ref "R7_1") (pin "1") (pinfunction "1_1") (pintype "passive"))
      (node (ref "TP_SAW1") (pin "P$1") (pinfunction "P$1_P$1") (pintype "passive"))
    )
    (net (code "171") (name "VCO3340B_TRI_OUT") (class "Default")
      (node (ref "3340B") (pin "10") (pinfunction "TRI_OUT_10") (pintype "bidirectional"))
      (node (ref "JP_TRIOUT_VCO3340B") (pin "1") (pinfunction "1_1") (pintype "passive"))
      (node (ref "TP_TRI1") (pin "P$1") (pinfunction "P$1_P$1") (pintype "passive"))
    )
    (net (code "172") (name "VCO13700_SQUARE") (class "Default")
      (node (ref "CIN_2") (pin "2") (pinfunction "2_2") (pintype "passive"))
      (node (ref "JP8") (pin "1") (pinfunction "1_1") (pintype "passive"))
      (node (ref "RSQU_2") (pin "2") (pinfunction "2_2") (pintype "passive"))
      (node (ref "TP_13700_SQU2") (pin "P$1") (pinfunction "P$1_P$1") (pintype "passive"))
      (node (ref "VCO2") (pin "9") (pinfunction "E_9") (pintype "passive"))
    )
    (net (code "173") (name "VCO13700_SUBBASS") (class "Default")
      (node (ref "JP7") (pin "1") (pinfunction "1_1") (pintype "passive"))
      (node (ref "RCAL_1") (pin "1") (pinfunction "1_1") (pintype "passive"))
      (node (ref "SUBBASS2") (pin "15") (pinfunction "1Q_15") (pintype "output"))
    )
    (net (code "174") (name "VCO13700_TRI") (class "Default")
      (node (ref "JP9") (pin "1") (pinfunction "1_1") (pintype "passive"))
      (node (ref "RTRI_2") (pin "2") (pinfunction "2_2") (pintype "passive"))
      (node (ref "TP_13700_TRI2") (pin "P$1") (pinfunction "P$1_P$1") (pintype "passive"))
      (node (ref "VCO2") (pin "13") (pinfunction "IN_N_13") (pintype "input"))
      (node (ref "VCO2") (pin "8") (pinfunction "E_8") (pintype "passive"))
    )
    (net (code "175") (name "VEE_VCF") (class "Default")
      (node (ref "C-15VPOL_VCF") (pin "1") (pinfunction "1_1") (pintype "passive"))
      (node (ref "C-15V_VCF") (pin "1") (pinfunction "1_1") (pintype "passive"))
      (node (ref "REE_VCF") (pin "2") (pinfunction "2_2") (pintype "passive"))
      (node (ref "VCF") (pin "13") (pinfunction "V-_13") (pintype "bidirectional"))
    )
    (net (code "176") (name "VEE_VCOA") (class "Default")
      (node (ref "3340A") (pin "3") (pinfunction "VEE_3") (pintype "bidirectional"))
      (node (ref "CDEC_3340B6") (pin "2") (pinfunction "2_2") (pintype "passive"))
      (node (ref "CDEC_3340B7") (pin "2") (pinfunction "2_2") (pintype "passive"))
      (node (ref "R1_4") (pin "2") (pinfunction "2_2") (pintype "passive"))
      (node (ref "R2_4") (pin "2") (pinfunction "2_2") (pintype "passive"))
      (node (ref "R3_3") (pin "2") (pinfunction "2_2") (pintype "passive"))
    )
    (net (code "177") (name "VEE_VCOB") (class "Default")
      (node (ref "3340B") (pin "3") (pinfunction "VEE_3") (pintype "bidirectional"))
      (node (ref "CDEC_3340B2") (pin "2") (pinfunction "2_2") (pintype "passive"))
      (node (ref "CDEC_3340B3") (pin "2") (pinfunction "2_2") (pintype "passive"))
      (node (ref "R1_3") (pin "2") (pinfunction "2_2") (pintype "passive"))
      (node (ref "R2_3") (pin "2") (pinfunction "2_2") (pintype "passive"))
      (node (ref "R3_1") (pin "2") (pinfunction "2_2") (pintype "passive"))
    )
    (net (code "178") (name "unconnected-(3340A-CURRENT_CORR-Pad7)") (class "Default")
      (node (ref "3340A") (pin "7") (pinfunction "CURRENT_CORR_7") (pintype "bidirectional"))
    )
    (net (code "179") (name "unconnected-(3340B-CURRENT_CORR-Pad7)") (class "Default")
      (node (ref "3340B") (pin "7") (pinfunction "CURRENT_CORR_7") (pintype "bidirectional"))
    )
    (net (code "180") (name "unconnected-(CONV_ITOV_OUT-CMP-Pad5)") (class "Default")
      (node (ref "CONV_ITOV_OUT") (pin "5") (pinfunction "CMP_5") (pintype "passive"))
    )
    (net (code "181") (name "unconnected-(CONV_ITOV_OUT-ON-Pad1)") (class "Default")
      (node (ref "CONV_ITOV_OUT") (pin "1") (pinfunction "ON_1") (pintype "passive"))
    )
    (net (code "182") (name "unconnected-(CONV_ITOV_OUT-ON{slash}CMP-Pad8)") (class "Default")
      (node (ref "CONV_ITOV_OUT") (pin "8") (pinfunction "ON/CMP_8") (pintype "passive"))
    )
    (net (code "183") (name "unconnected-(JP_FMLIN_VCO3340B1-Pad2)") (class "Default")
      (node (ref "JP_FMLIN_VCO3340B1") (pin "2") (pinfunction "2_2") (pintype "passive"))
    )
    (net (code "184") (name "unconnected-(JP_MIXER_B-Pad2)") (class "Default")
      (node (ref "JP_MIXER_B") (pin "2") (pinfunction "2_2") (pintype "passive"))
    )
    (net (code "185") (name "unconnected-(OPAMP_SUM_STG-CMP-Pad5)") (class "Default")
      (node (ref "OPAMP_SUM_STG") (pin "5") (pinfunction "CMP_5") (pintype "passive"))
    )
    (net (code "186") (name "unconnected-(OPAMP_SUM_STG-ON-Pad1)") (class "Default")
      (node (ref "OPAMP_SUM_STG") (pin "1") (pinfunction "ON_1") (pintype "passive"))
    )
    (net (code "187") (name "unconnected-(OPAMP_SUM_STG-ON{slash}CMP-Pad8)") (class "Default")
      (node (ref "OPAMP_SUM_STG") (pin "8") (pinfunction "ON/CMP_8") (pintype "passive"))
    )
    (net (code "188") (name "unconnected-(STM32L432KC_CONN_A-NRST-Pad3.3)") (class "Default")
      (node (ref "STM32L432KC_CONN_") (pin "3.3") (pinfunction "NRST_3.3") (pintype "bidirectional"))
    )
    (net (code "189") (name "unconnected-(STM32L432KC_CONN_B-+3V3-Pad4.14)") (class "Default")
      (node (ref "STM32L432KC_CONN_") (pin "4.14") (pinfunction "+3V3_4.14") (pintype "bidirectional"))
    )
    (net (code "190") (name "unconnected-(STM32L432KC_CONN_B-+5V-Pad4.4)") (class "Default")
      (node (ref "STM32L432KC_CONN_") (pin "4.4") (pinfunction "+5V_4.4") (pintype "bidirectional"))
    )
    (net (code "191") (name "unconnected-(STM32L432KC_CONN_B-AREF-Pad4.13)") (class "Default")
      (node (ref "STM32L432KC_CONN_") (pin "4.13") (pinfunction "AREF_4.13") (pintype "bidirectional"))
    )
    (net (code "192") (name "unconnected-(STM32L432KC_CONN_B-NRST-Pad4.3)") (class "Default")
      (node (ref "STM32L432KC_CONN_") (pin "4.3") (pinfunction "NRST_4.3") (pintype "bidirectional"))
    )
    (net (code "193") (name "unconnected-(STM32L432KC_CONN_B-PA0-Pad4.12)") (class "Default")
      (node (ref "STM32L432KC_CONN_") (pin "4.12") (pinfunction "PA0_4.12") (pintype "bidirectional"))
    )
    (net (code "194") (name "unconnected-(STM32L432KC_CONN_B-PA2-Pad4.5)") (class "Default")
      (node (ref "STM32L432KC_CONN_") (pin "4.5") (pinfunction "PA2_4.5") (pintype "bidirectional"))
    )
    (net (code "195") (name "unconnected-(SUBBASS2-2CD-Pad4)") (class "Default")
      (node (ref "SUBBASS2") (pin "4") (pinfunction "2CD_4") (pintype "input"))
    )
    (net (code "196") (name "unconnected-(SUBBASS2-2CP-Pad3)") (class "Default")
      (node (ref "SUBBASS2") (pin "3") (pinfunction "2CP_3") (pintype "input"))
    )
    (net (code "197") (name "unconnected-(SUBBASS2-2J-Pad6)") (class "Default")
      (node (ref "SUBBASS2") (pin "6") (pinfunction "2J_6") (pintype "input"))
    )
    (net (code "198") (name "unconnected-(SUBBASS2-2K-Pad5)") (class "Default")
      (node (ref "SUBBASS2") (pin "5") (pinfunction "2K_5") (pintype "input"))
    )
    (net (code "199") (name "unconnected-(SUBBASS2-2Q-Pad1)") (class "Default")
      (node (ref "SUBBASS2") (pin "1") (pinfunction "2Q_1") (pintype "output"))
    )
    (net (code "200") (name "unconnected-(SUBBASS2-2SD-Pad7)") (class "Default")
      (node (ref "SUBBASS2") (pin "7") (pinfunction "2SD_7") (pintype "input"))
    )
    (net (code "201") (name "unconnected-(SUBBASS2-2~{Q}-Pad2)") (class "Default")
      (node (ref "SUBBASS2") (pin "2") (pinfunction "2~{Q}_2") (pintype "output"))
    )
    (net (code "202") (name "unconnected-(U1A-1_NC-Pad2)") (class "Default")
      (node (ref "U1") (pin "2") (pinfunction "1_NC_2") (pintype "passive"))
    )
    (net (code "203") (name "unconnected-(U1A-2_NC-Pad3)") (class "Default")
      (node (ref "U1") (pin "3") (pinfunction "2_NC_3") (pintype "passive"))
    )
    (net (code "204") (name "unconnected-(U1A-3_NC-Pad33)") (class "Default")
      (node (ref "U1") (pin "33") (pinfunction "3_NC_33") (pintype "passive"))
    )
    (net (code "205") (name "unconnected-(U1A-4_NC-Pad34)") (class "Default")
      (node (ref "U1") (pin "34") (pinfunction "4_NC_34") (pintype "passive"))
    )
    (net (code "206") (name "unconnected-(U1A-5_NC-Pad35)") (class "Default")
      (node (ref "U1") (pin "35") (pinfunction "5_NC_35") (pintype "passive"))
    )
    (net (code "207") (name "unconnected-(U1A-6_NC-Pad36)") (class "Default")
      (node (ref "U1") (pin "36") (pinfunction "6_NC_36") (pintype "passive"))
    )
    (net (code "208") (name "unconnected-(U1A-MON_IN1-Pad18)") (class "Default")
      (node (ref "U1") (pin "18") (pinfunction "MON_IN1_18") (pintype "input"))
    )
    (net (code "209") (name "unconnected-(U1A-MON_IN2-Pad19)") (class "Default")
      (node (ref "U1") (pin "19") (pinfunction "MON_IN2_19") (pintype "input"))
    )
    (net (code "210") (name "unconnected-(U1A-MON_OUT-Pad20)") (class "Default")
      (node (ref "U1") (pin "20") (pinfunction "MON_OUT_20") (pintype "tri_state"))
    )
    (net (code "211") (name "unconnected-(U1A-SDO-Pad48)") (class "Default")
      (node (ref "U1") (pin "48") (pinfunction "SDO_48") (pintype "tri_state"))
    )
    (net (code "212") (name "unconnected-(U1A-~{BUSY}-Pad38)") (class "Default")
      (node (ref "U1") (pin "38") (pinfunction "~{BUSY}_38") (pintype "output"))
    )
    (net (code "213") (name "unconnected-(VCAC-I_DIODE-Pad2)") (class "Default")
      (node (ref "VCA") (pin "2") (pinfunction "I_DIODE_2") (pintype "input"))
    )
    (net (code "214") (name "unconnected-(VCO2C-I_DIODE-Pad2)") (class "Default")
      (node (ref "VCO2") (pin "2") (pinfunction "I_DIODE_2") (pintype "input"))
    )
    (net (code "215") (name "unconnected-(VCO2D-I_DIODE-Pad15)") (class "Default")
      (node (ref "VCO2") (pin "15") (pinfunction "I_DIODE_15") (pintype "input"))
    )
  )
)
